# Titan_v1p0.net
KiCad netlist of a schematic drawn in EAGLE
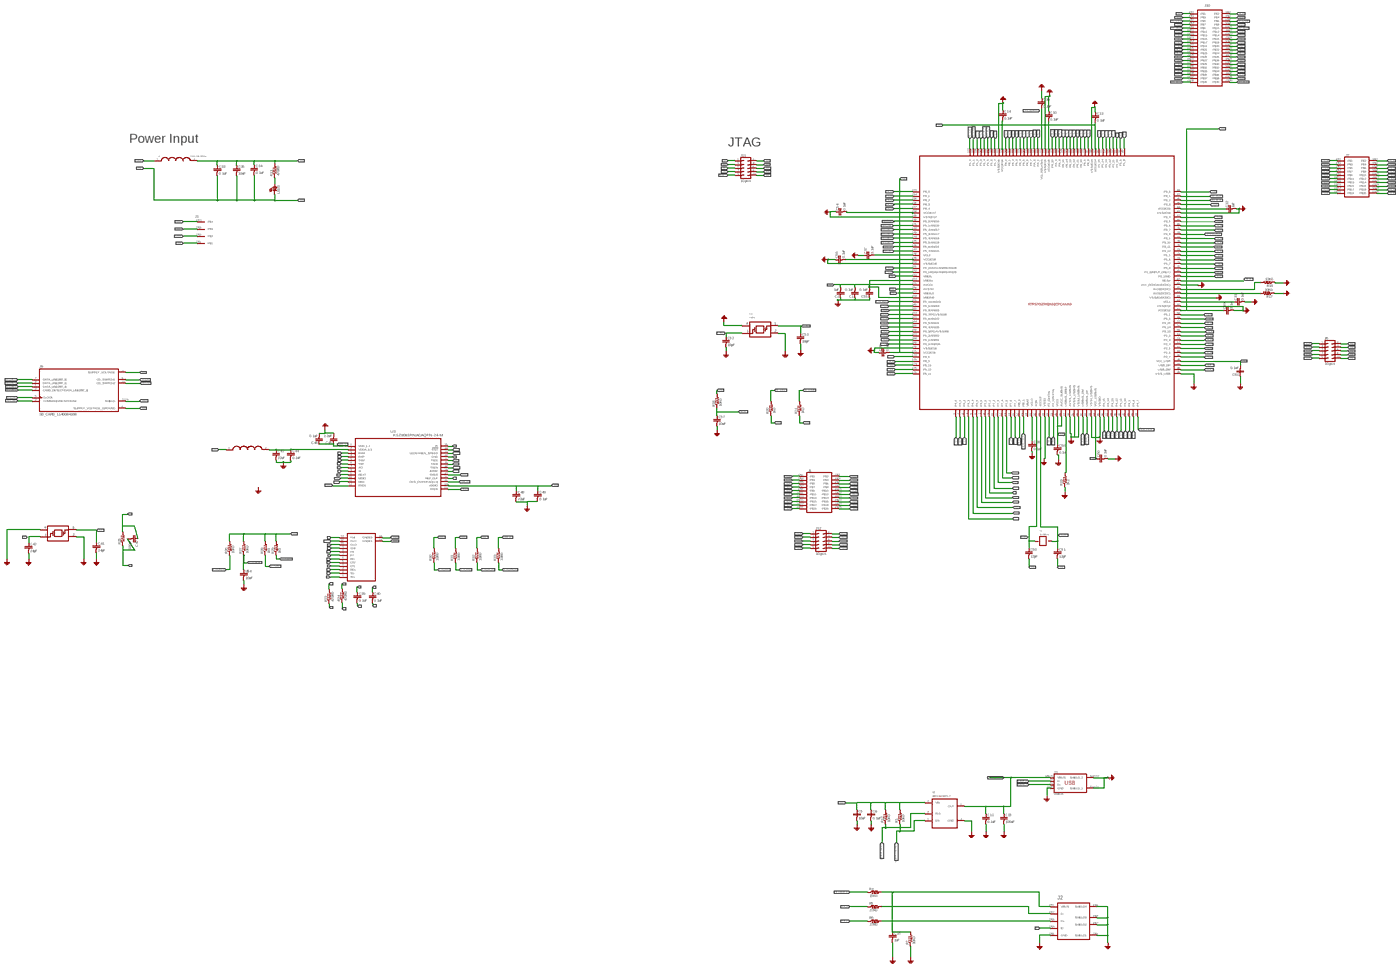
[diagram p0: schematic, sheet 1, overview]
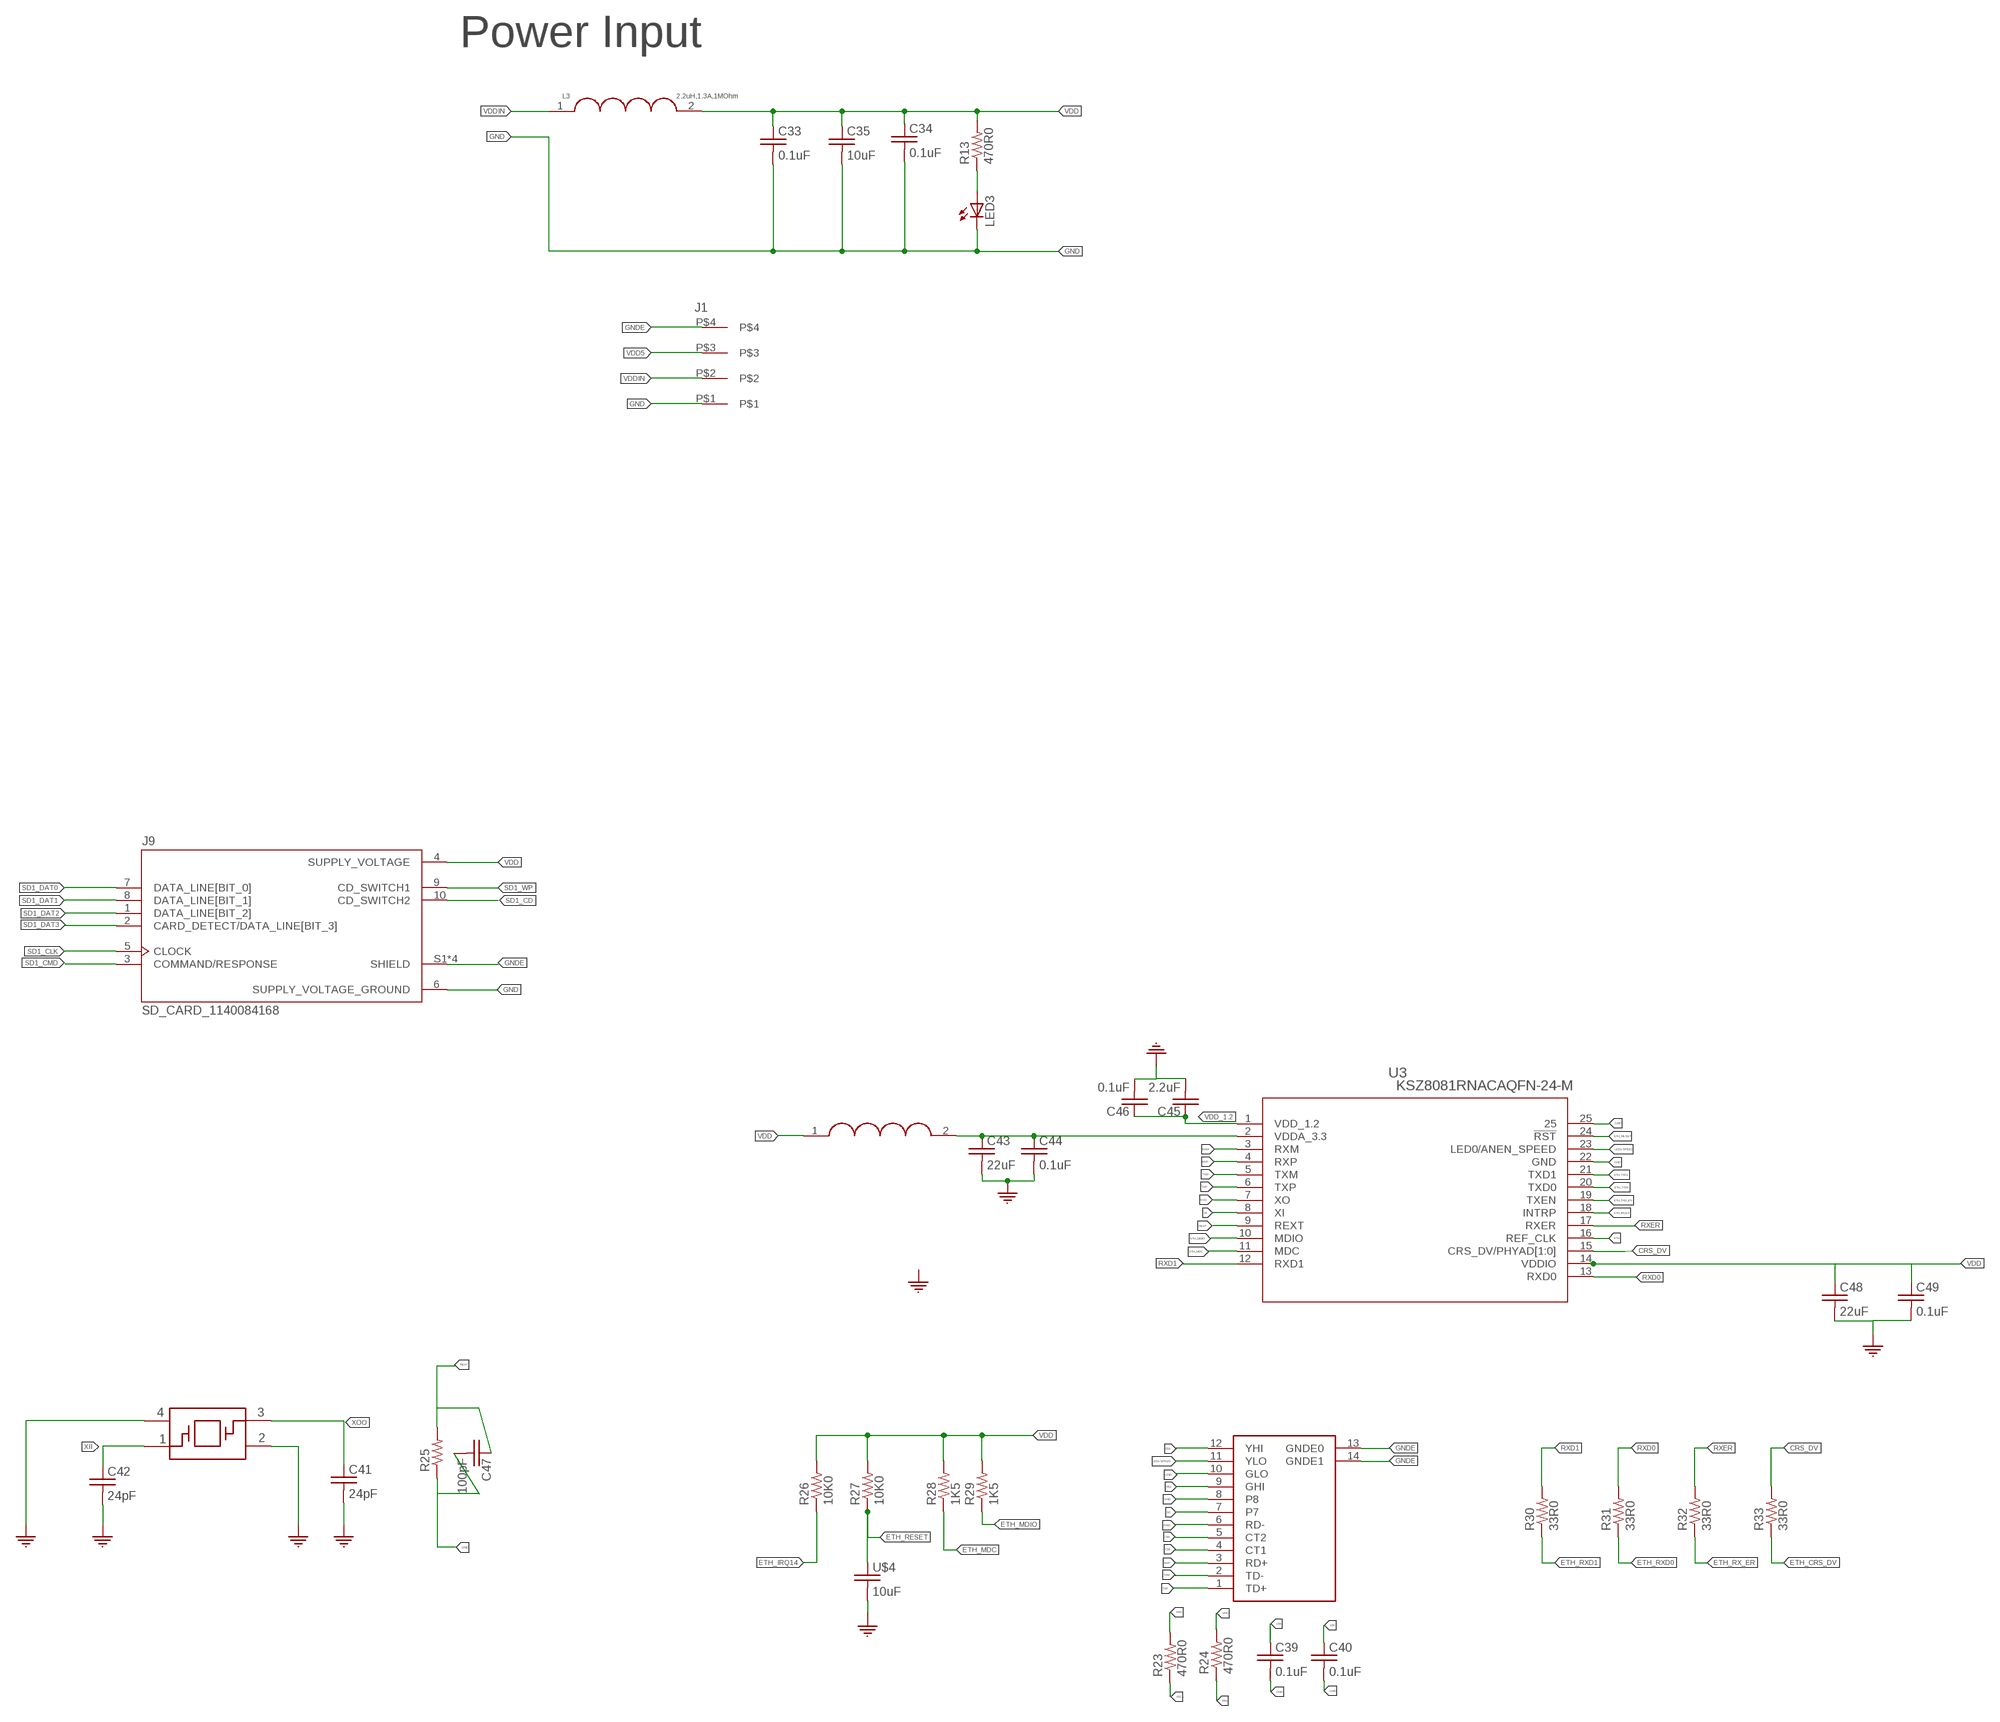
[diagram p1: schematic, sheet 1, part 1 of 4]
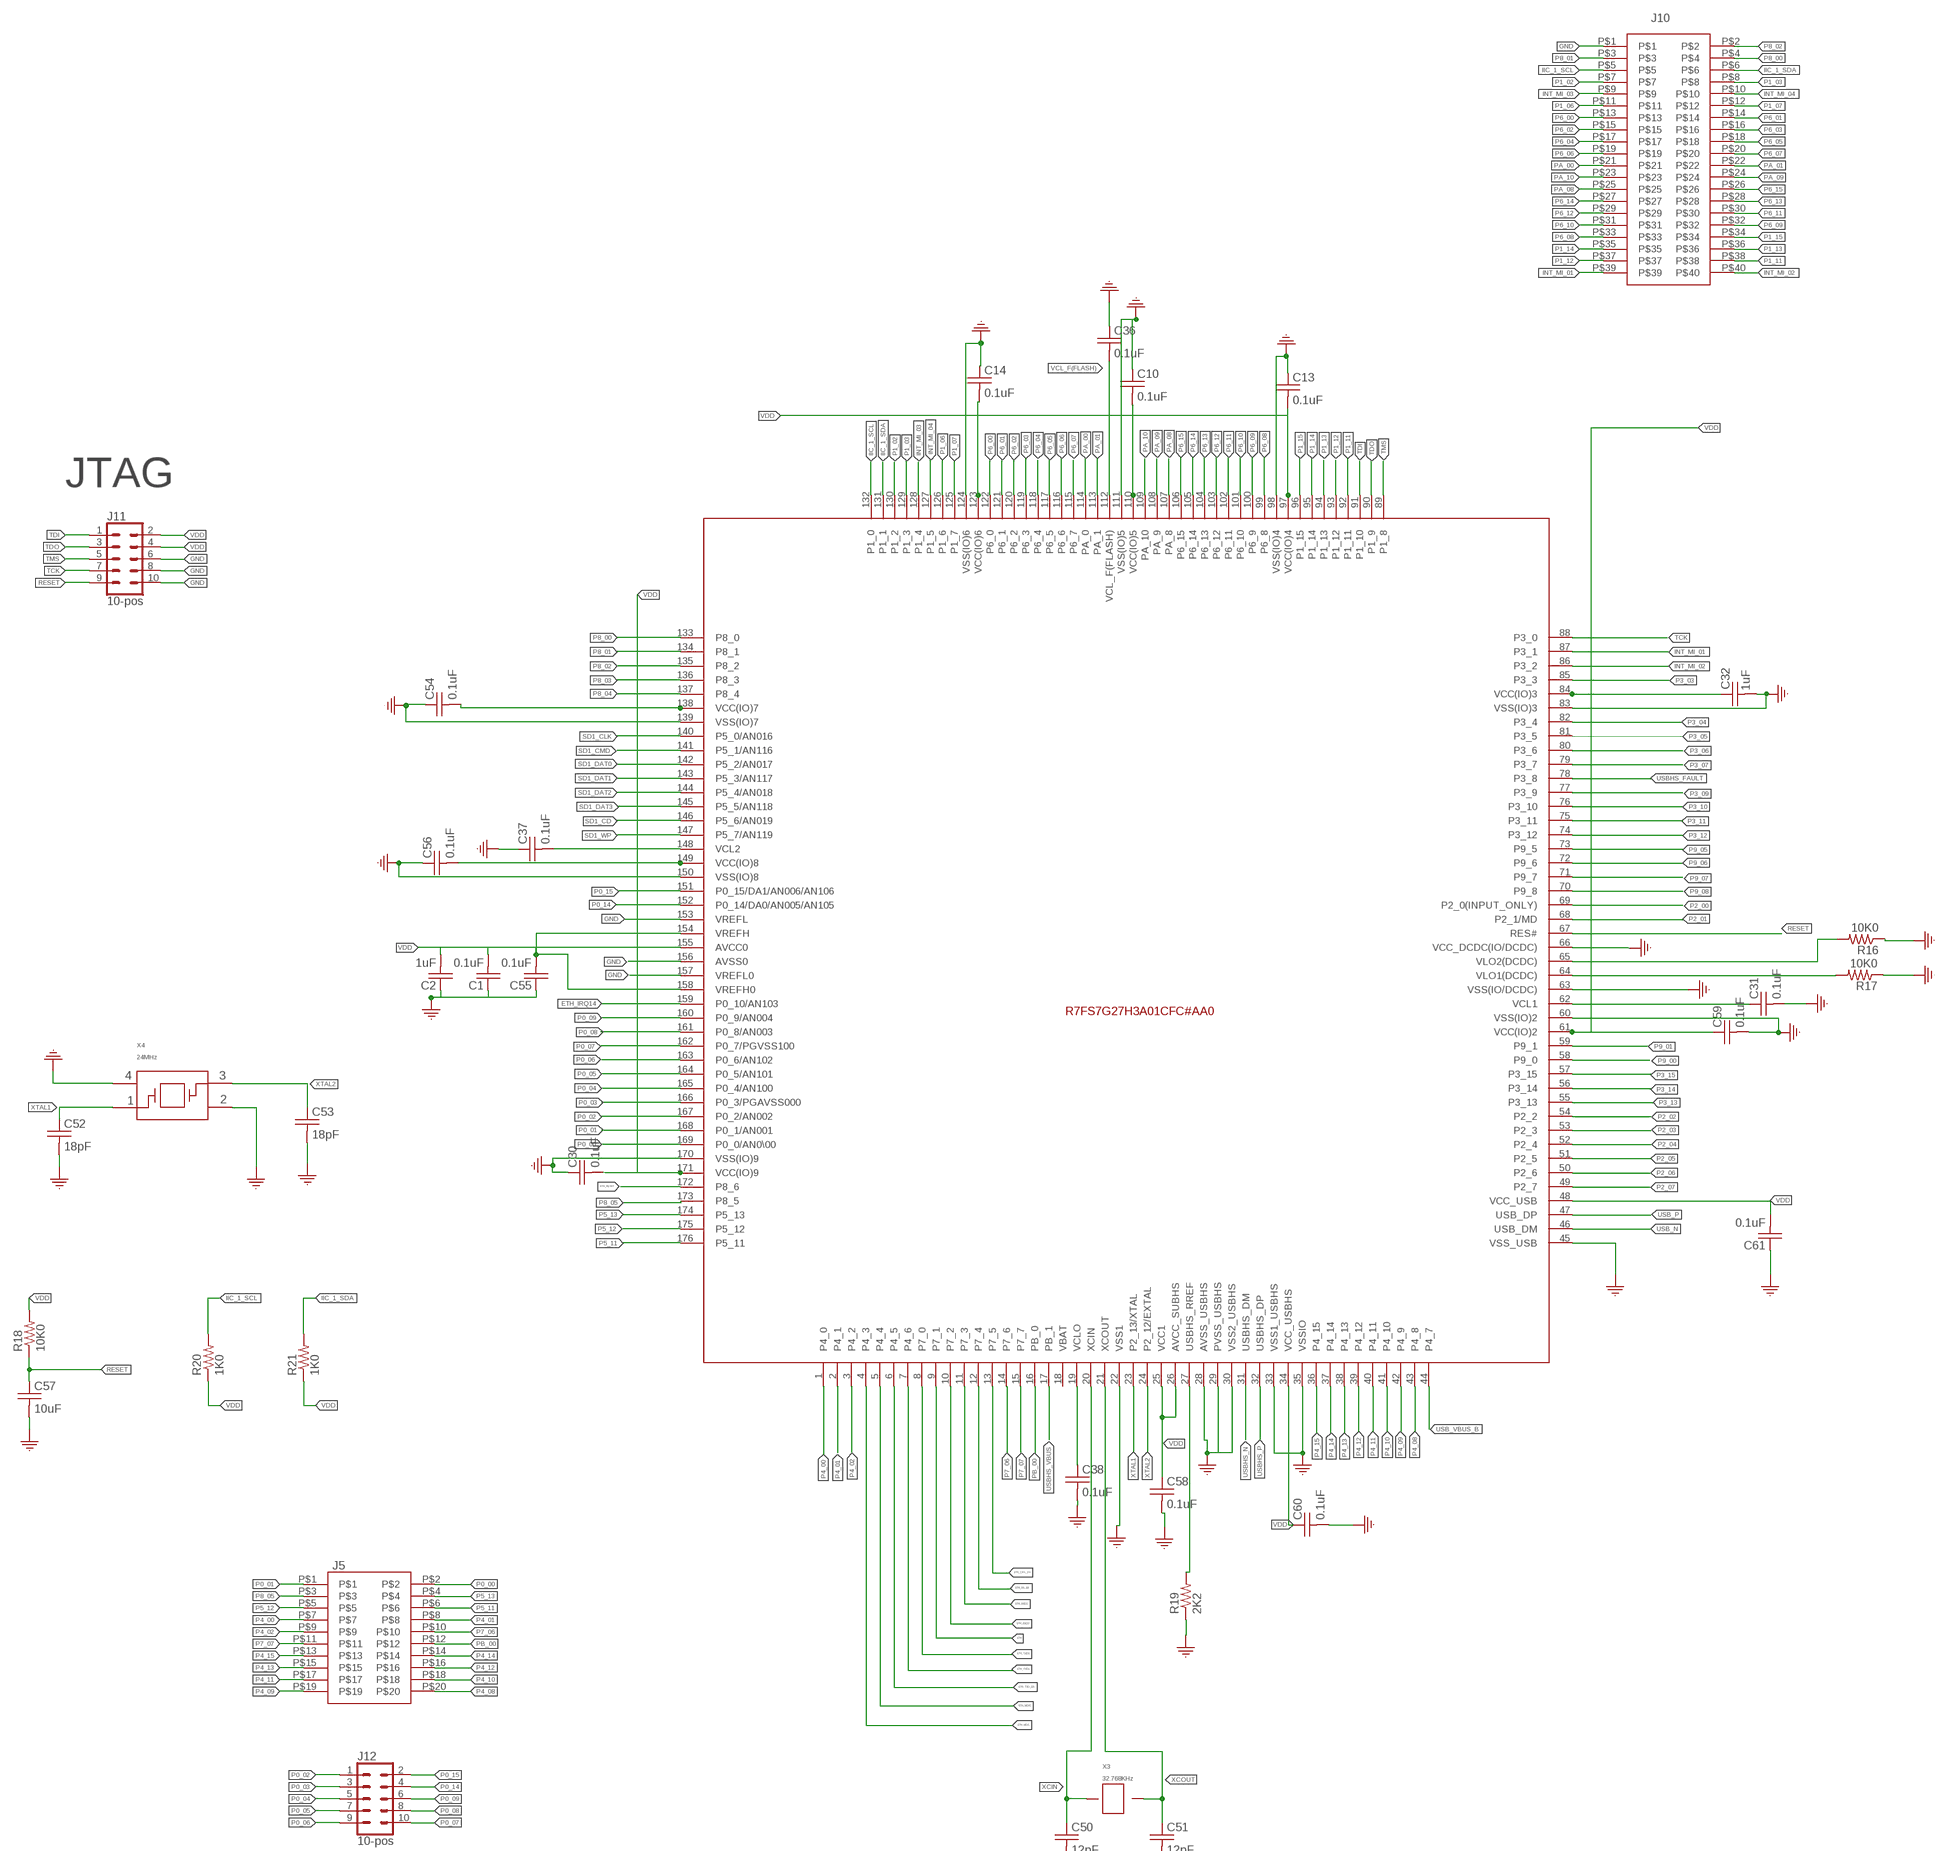
[diagram p2: schematic, sheet 1, part 2 of 4]
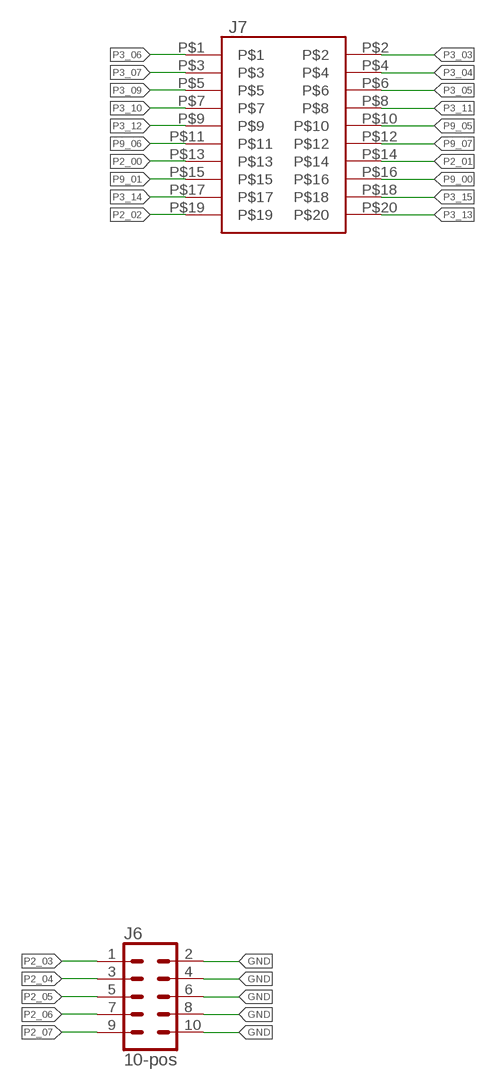
[diagram p3: schematic, sheet 1, part 3 of 4]
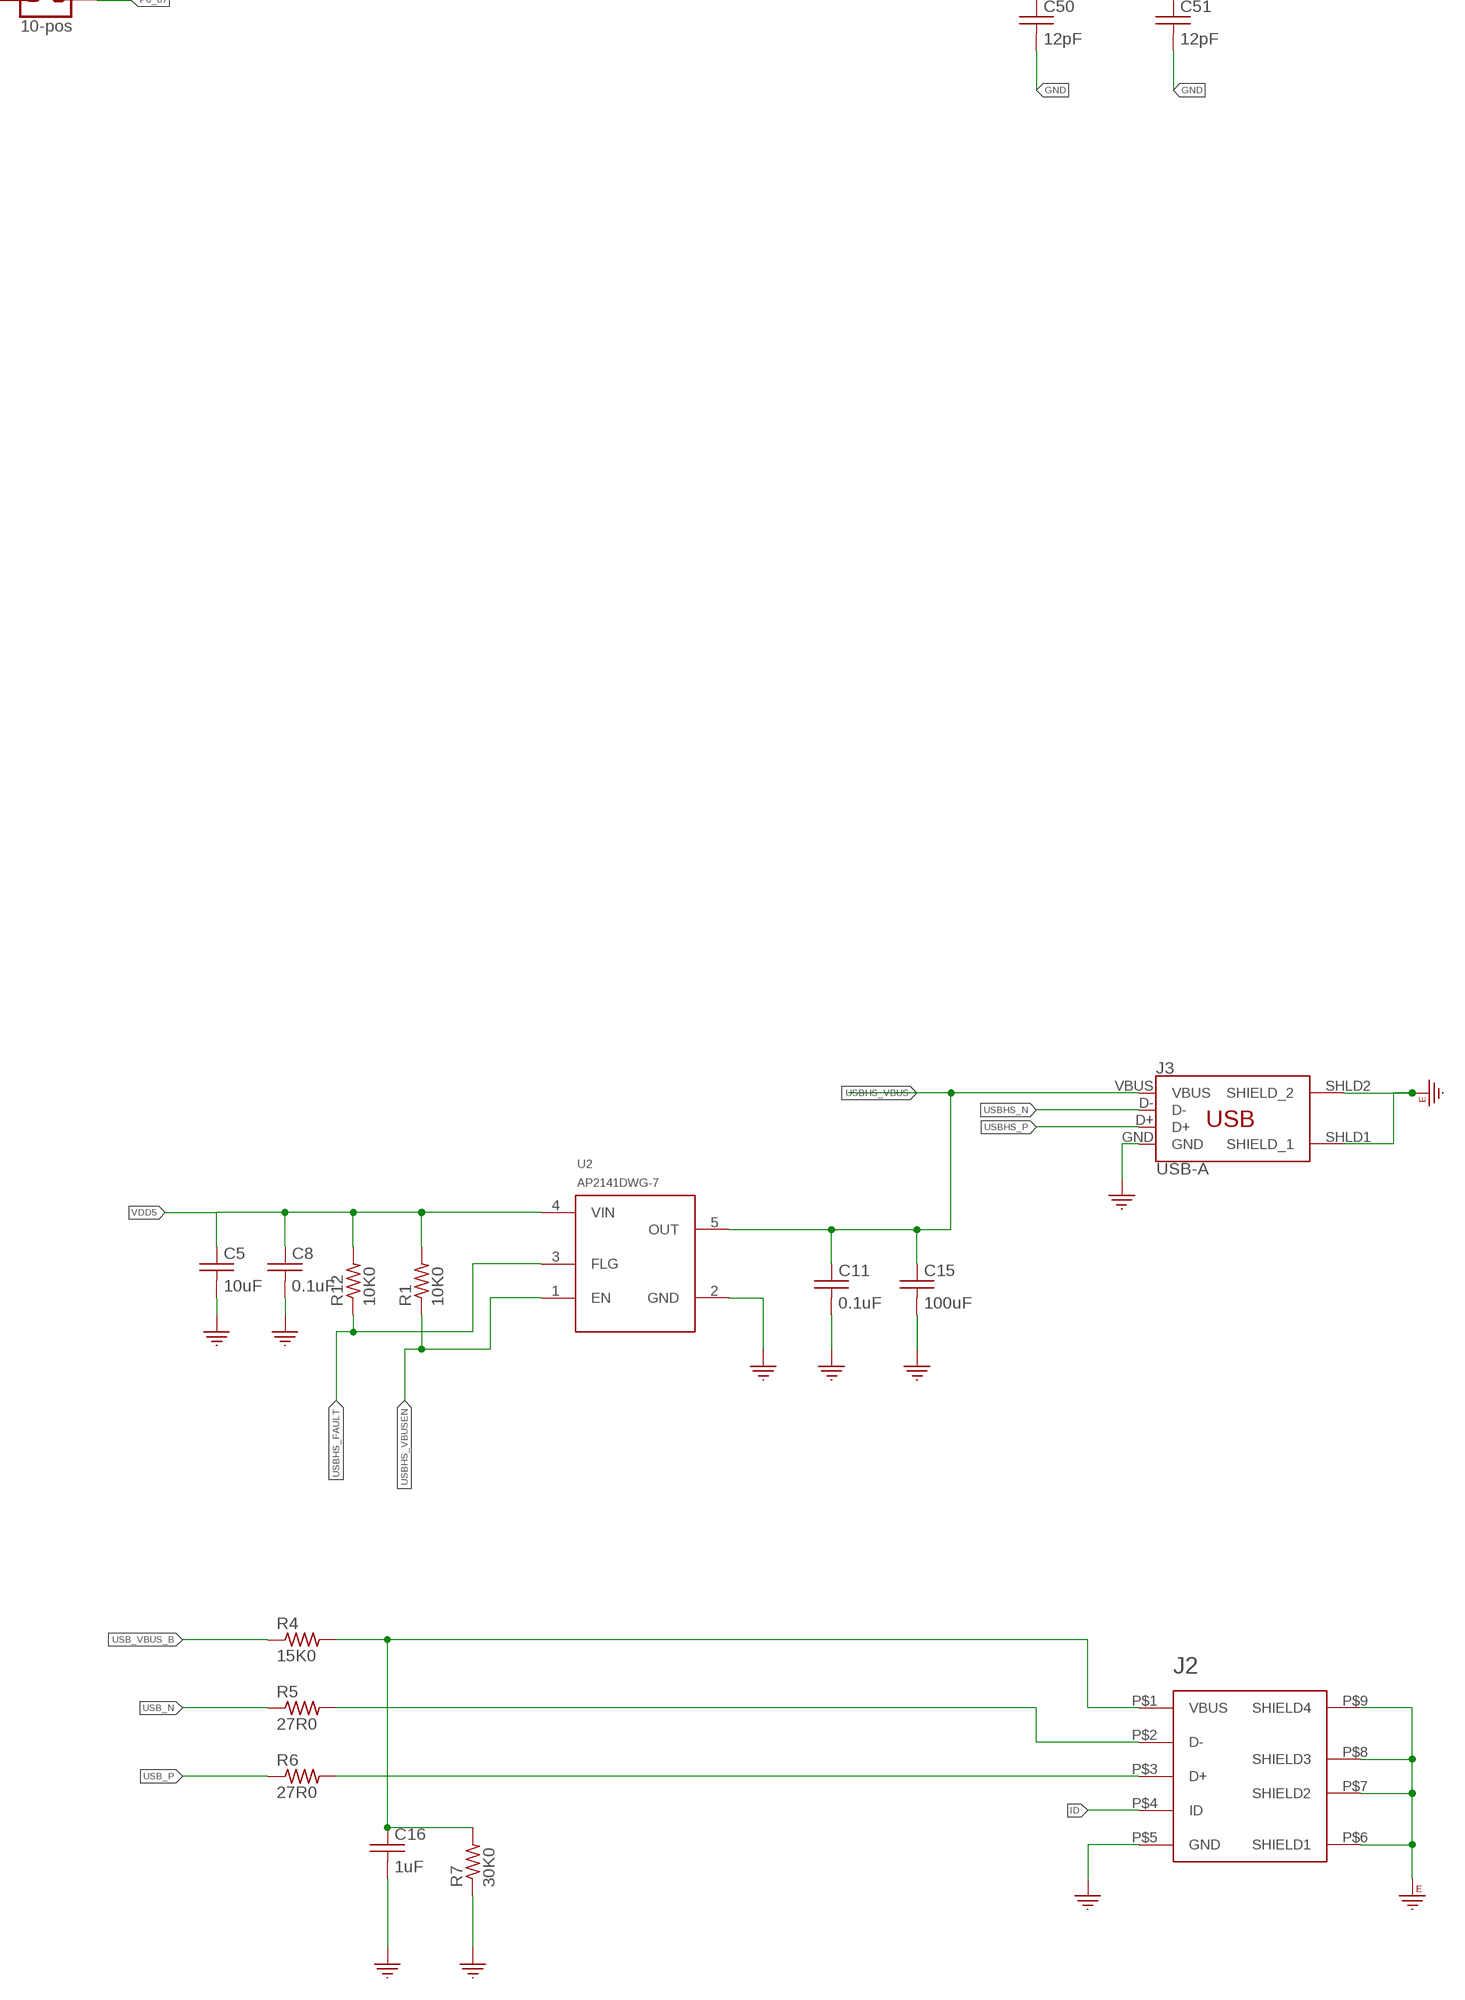
[diagram p4: schematic, sheet 1, part 4 of 4]

(export (version "E")
  (design (tool "Eeschema 10.0.6"))
  (components
    (comp (ref "C1")
      (value "0.1uF")
      (footprint "eagle-import:0402")
      (fields (field (name "PARTNO") "CL05F104ZO5NNNC"))
      (libsource (lib "eagle-import") (part "C_0402_0.1UF"))
    )
    (comp (ref "C2")
      (value "1uF")
      (footprint "eagle-import:0402")
      (fields (field (name "PARTNO") "CL05A105KO5NNNC"))
      (libsource (lib "eagle-import") (part "C_0402_1UF"))
    )
    (comp (ref "C5")
      (value "10uF")
      (footprint "eagle-import:0402")
      (fields (field (name "PARTNO") "CL05A106MP8NUB8"))
      (libsource (lib "eagle-import") (part "C_0402_10UF"))
    )
    (comp (ref "C8")
      (value "0.1uF")
      (footprint "eagle-import:0402")
      (fields (field (name "PARTNO") "CL05F104ZO5NNNC"))
      (libsource (lib "eagle-import") (part "C_0402_0.1UF"))
    )
    (comp (ref "C10")
      (value "0.1uF")
      (footprint "eagle-import:0402")
      (fields (field (name "PARTNO") "CL05F104ZO5NNNC"))
      (libsource (lib "eagle-import") (part "C_0402_0.1UF"))
    )
    (comp (ref "C11")
      (value "0.1uF")
      (footprint "eagle-import:0402")
      (fields (field (name "PARTNO") "CL05F104ZO5NNNC"))
      (libsource (lib "eagle-import") (part "C_0402_0.1UF"))
    )
    (comp (ref "C13")
      (value "0.1uF")
      (footprint "eagle-import:0402")
      (fields (field (name "PARTNO") "CL05F104ZO5NNNC"))
      (libsource (lib "eagle-import") (part "C_0402_0.1UF"))
    )
    (comp (ref "C14")
      (value "0.1uF")
      (footprint "eagle-import:0402")
      (fields (field (name "PARTNO") "CL05F104ZO5NNNC"))
      (libsource (lib "eagle-import") (part "C_0402_0.1UF"))
    )
    (comp (ref "C15")
      (value "100uF")
      (footprint "eagle-import:C1210")
      (fields (field (name "PARTNO") "TL8A0107M010D"))
      (libsource (lib "eagle-import") (part "C_1210"))
    )
    (comp (ref "C16")
      (value "1uF")
      (footprint "eagle-import:0402")
      (fields (field (name "PARTNO") "CL05A105KO5NNNC"))
      (libsource (lib "eagle-import") (part "C_0402_1UF"))
    )
    (comp (ref "C30")
      (value "0.1uF")
      (footprint "eagle-import:0402")
      (fields (field (name "PARTNO") "CL05F104ZO5NNNC"))
      (libsource (lib "eagle-import") (part "C_0402_0.1UF"))
    )
    (comp (ref "C31")
      (value "0.1uF")
      (footprint "eagle-import:0402")
      (fields (field (name "PARTNO") "CL05F104ZO5NNNC"))
      (libsource (lib "eagle-import") (part "C_0402_0.1UF"))
    )
    (comp (ref "C32")
      (value "1uF")
      (footprint "eagle-import:0402")
      (fields (field (name "PARTNO") "CL05A105KO5NNNC"))
      (libsource (lib "eagle-import") (part "C_0402_1UF"))
    )
    (comp (ref "C33")
      (value "0.1uF")
      (footprint "eagle-import:0402")
      (fields (field (name "PARTNO") "CL05F104ZO5NNNC"))
      (libsource (lib "eagle-import") (part "C_0402_0.1UF"))
    )
    (comp (ref "C34")
      (value "0.1uF")
      (footprint "eagle-import:0402")
      (fields (field (name "PARTNO") "CL05F104ZO5NNNC"))
      (libsource (lib "eagle-import") (part "C_0402_0.1UF"))
    )
    (comp (ref "C35")
      (value "10uF")
      (footprint "eagle-import:0402")
      (fields (field (name "PARTNO") "CL05A106MP8NUB8"))
      (libsource (lib "eagle-import") (part "C_0402_10UF"))
    )
    (comp (ref "C36")
      (value "0.1uF")
      (footprint "eagle-import:0402")
      (fields (field (name "PARTNO") "CL05F104ZO5NNNC"))
      (libsource (lib "eagle-import") (part "C_0402_0.1UF"))
    )
    (comp (ref "C37")
      (value "0.1uF")
      (footprint "eagle-import:0402")
      (fields (field (name "PARTNO") "CL05F104ZO5NNNC"))
      (libsource (lib "eagle-import") (part "C_0402_0.1UF"))
    )
    (comp (ref "C38")
      (value "0.1uF")
      (footprint "eagle-import:0402")
      (fields (field (name "PARTNO") "CL05F104ZO5NNNC"))
      (libsource (lib "eagle-import") (part "C_0402_0.1UF"))
    )
    (comp (ref "C39")
      (value "0.1uF")
      (footprint "eagle-import:0402")
      (fields (field (name "PARTNO") "CL05F104ZO5NNNC"))
      (libsource (lib "eagle-import") (part "C_0402_0.1UF"))
    )
    (comp (ref "C40")
      (value "0.1uF")
      (footprint "eagle-import:0402")
      (fields (field (name "PARTNO") "CL05F104ZO5NNNC"))
      (libsource (lib "eagle-import") (part "C_0402_0.1UF"))
    )
    (comp (ref "C41")
      (value "24pF")
      (footprint "eagle-import:0402")
      (fields (field (name "PARTNO") "CC0402GRNPO9BN240"))
      (libsource (lib "eagle-import") (part "C_0402_24PF"))
    )
    (comp (ref "C42")
      (value "24pF")
      (footprint "eagle-import:0402")
      (fields (field (name "PARTNO") "CC0402GRNPO9BN240"))
      (libsource (lib "eagle-import") (part "C_0402_24PF"))
    )
    (comp (ref "C43")
      (value "22uF")
      (footprint "eagle-import:0402")
      (fields (field (name "PARTNO") "CL05A226MQ5N6J8"))
      (libsource (lib "eagle-import") (part "C_0402_22UF"))
    )
    (comp (ref "C44")
      (value "0.1uF")
      (footprint "eagle-import:0402")
      (fields (field (name "PARTNO") "CL05F104ZO5NNNC"))
      (libsource (lib "eagle-import") (part "C_0402_0.1UF"))
    )
    (comp (ref "C45")
      (value "2.2uF")
      (footprint "eagle-import:0402")
      (fields (field (name "PARTNO") "GRM155C81C225ME15D"))
      (libsource (lib "eagle-import") (part "C_0402_2.2UF"))
    )
    (comp (ref "C46")
      (value "0.1uF")
      (footprint "eagle-import:0402")
      (fields (field (name "PARTNO") "CL05F104ZO5NNNC"))
      (libsource (lib "eagle-import") (part "C_0402_0.1UF"))
    )
    (comp (ref "C47")
      (value "100pF")
      (footprint "eagle-import:0402")
      (fields (field (name "PARTNO") "CL05C101JB5NNNC"))
      (libsource (lib "eagle-import") (part "C_0402_100PF"))
    )
    (comp (ref "C48")
      (value "22uF")
      (footprint "eagle-import:0402")
      (fields (field (name "PARTNO") "CL05A226MQ5N6J8"))
      (libsource (lib "eagle-import") (part "C_0402_22UF"))
    )
    (comp (ref "C49")
      (value "0.1uF")
      (footprint "eagle-import:0402")
      (fields (field (name "PARTNO") "CL05F104ZO5NNNC"))
      (libsource (lib "eagle-import") (part "C_0402_0.1UF"))
    )
    (comp (ref "C50")
      (value "12pF")
      (footprint "eagle-import:0402")
      (fields (field (name "PARTNO") "CL05C120JB5NNNC"))
      (libsource (lib "eagle-import") (part "C_0402_12PF"))
    )
    (comp (ref "C51")
      (value "12pF")
      (footprint "eagle-import:0402")
      (fields (field (name "PARTNO") "CL05C120JB5NNNC"))
      (libsource (lib "eagle-import") (part "C_0402_12PF"))
    )
    (comp (ref "C52")
      (value "18pF")
      (footprint "eagle-import:0402")
      (fields (field (name "PARTNO") "UMK105CG180JV-F"))
      (libsource (lib "eagle-import") (part "C_0402_18PF"))
    )
    (comp (ref "C53")
      (value "18pF")
      (footprint "eagle-import:0402")
      (fields (field (name "PARTNO") "UMK105CG180JV-F"))
      (libsource (lib "eagle-import") (part "C_0402_18PF"))
    )
    (comp (ref "C54")
      (value "0.1uF")
      (footprint "eagle-import:0402")
      (fields (field (name "PARTNO") "CL05F104ZO5NNNC"))
      (libsource (lib "eagle-import") (part "C_0402_0.1UF"))
    )
    (comp (ref "C55")
      (value "0.1uF")
      (footprint "eagle-import:0402")
      (fields (field (name "PARTNO") "CL05F104ZO5NNNC"))
      (libsource (lib "eagle-import") (part "C_0402_0.1UF"))
    )
    (comp (ref "C56")
      (value "0.1uF")
      (footprint "eagle-import:0402")
      (fields (field (name "PARTNO") "CL05F104ZO5NNNC"))
      (libsource (lib "eagle-import") (part "C_0402_0.1UF"))
    )
    (comp (ref "C57")
      (value "10uF")
      (footprint "eagle-import:0402")
      (fields (field (name "PARTNO") "CL05A106MP8NUB8"))
      (libsource (lib "eagle-import") (part "C_0402_10UF"))
    )
    (comp (ref "C58")
      (value "0.1uF")
      (footprint "eagle-import:0402")
      (fields (field (name "PARTNO") "CL05F104ZO5NNNC"))
      (libsource (lib "eagle-import") (part "C_0402_0.1UF"))
    )
    (comp (ref "C59")
      (value "0.1uF")
      (footprint "eagle-import:0402")
      (fields (field (name "PARTNO") "CL05F104ZO5NNNC"))
      (libsource (lib "eagle-import") (part "C_0402_0.1UF"))
    )
    (comp (ref "C60")
      (value "0.1uF")
      (footprint "eagle-import:0402")
      (fields (field (name "PARTNO") "CL05F104ZO5NNNC"))
      (libsource (lib "eagle-import") (part "C_0402_0.1UF"))
    )
    (comp (ref "C61")
      (value "0.1uF")
      (footprint "eagle-import:0402")
      (fields (field (name "PARTNO") "CL05F104ZO5NNNC"))
      (libsource (lib "eagle-import") (part "C_0402_0.1UF"))
    )
    (comp (ref "FB2/2")
      (value "120Ohm")
      (footprint "eagle-import:0603")
      (fields (field (name "PARTNO") "BLM18PG121SN1D"))
      (libsource (lib "eagle-import") (part "FB_0603_120_OHM0603"))
    )
    (comp (ref "J1")
      (value "4-pos")
      (footprint "eagle-import:1X4_3.81MM_PITCH")
      (fields (field (name "PARTNO") "691322310004"))
      (libsource (lib "eagle-import") (part "3.81MM_1_X_4_RT_ANGLE_PLUG_HEADER"))
    )
    (comp (ref "J2")
      (value "USB-B-Micro")
      (footprint "eagle-import:USB_MICRO-B")
      (fields (field (name "PARTNO") "10118192-0002LF"))
      (libsource (lib "eagle-import") (part "USB_MICRO-B"))
    )
    (comp (ref "J3")
      (value "USB-A")
      (footprint "eagle-import:USB_A_SMT")
      (fields (field (name "PARTNO") "87583-3010RPALF"))
      (libsource (lib "eagle-import") (part "USB_A"))
    )
    (comp (ref "J4")
      (value "RJ45")
      (footprint "eagle-import:RJ45_TH_ELEC")
      (fields (field (name "PARTNO") "13F-64GYD2PL2NL"))
      (libsource (lib "eagle-import") (part "RJ45_WITH_ELEC"))
    )
    (comp (ref "J5")
      (value "20-pos")
      (footprint "eagle-import:2_X_10_.1_INCH")
      (fields (field (name "PARTNO") "67996-420HLF"))
      (libsource (lib "eagle-import") (part "2_X_10_HEADER_GENERIC"))
    )
    (comp (ref "J6")
      (value "10-pos")
      (footprint "eagle-import:2X5")
      (fields (field (name "PARTNO") "PH2RA-10-UA"))
      (libsource (lib "eagle-import") (part "CONN_05X2_RAPTH"))
    )
    (comp (ref "J7")
      (value "20-pos")
      (footprint "eagle-import:2_X_10_.1_INCH")
      (fields (field (name "PARTNO") "67996-420HLF"))
      (libsource (lib "eagle-import") (part "2_X_10_HEADER_GENERIC"))
    )
    (comp (ref "J9")
      (value "SD_CARD_1140084168")
      (footprint "eagle-import:AMPHENOL_1140084168")
      (fields (field (name "MF") "Amphenol ICC") (field (name "PARTNO") "114-00841-68"))
      (libsource (lib "eagle-import") (part "SD_CARD_1140084168"))
    )
    (comp (ref "J10")
      (value "40-pos")
      (footprint "eagle-import:HEADER_2_X_20_.1_INCH")
      (fields (field (name "PARTNO") "61304021021"))
      (libsource (lib "eagle-import") (part "HEADER_2_X_20_GENERIC"))
    )
    (comp (ref "J11")
      (value "10-pos")
      (footprint "eagle-import:2X5")
      (fields (field (name "PARTNO") "PH2RA-10-UA"))
      (libsource (lib "eagle-import") (part "CONN_05X2_RAPTH"))
    )
    (comp (ref "J12")
      (value "10-pos")
      (footprint "eagle-import:2X5")
      (fields (field (name "PARTNO") "PH2RA-10-UA"))
      (libsource (lib "eagle-import") (part "CONN_05X2_RAPTH"))
    )
    (comp (ref "L3")
      (value "2.2uH,1.3A,1MOhm")
      (footprint "eagle-import:1008")
      (fields (field (name "PARTNO") "LQM2HPN2R2MG0L"))
      (libsource (lib "eagle-import") (part "INDUCTOR_1008_2.2_MH_1.3A"))
    )
    (comp (ref "LED3")
      (value "Green")
      (footprint "eagle-import:0805")
      (fields (field (name "PARTNO") "LG R971-KN-1"))
      (libsource (lib "eagle-import") (part "LED_0805_GREEN"))
    )
    (comp (ref "R1")
      (value "10K0")
      (footprint "eagle-import:0402")
      (fields (field (name "PARTNO") "RMCF0402JT10K0"))
      (libsource (lib "eagle-import") (part "R_0402_10K0"))
    )
    (comp (ref "R4")
      (value "15K0")
      (footprint "eagle-import:0402")
      (fields (field (name "PARTNO") "RMCF0402JT15K0"))
      (libsource (lib "eagle-import") (part "R_0402_15K0"))
    )
    (comp (ref "R5")
      (value "27R0")
      (footprint "eagle-import:0402")
      (fields (field (name "PARTNO") "RMCF0402JT27R0"))
      (libsource (lib "eagle-import") (part "R_0402_27R0"))
    )
    (comp (ref "R6")
      (value "27R0")
      (footprint "eagle-import:0402")
      (fields (field (name "PARTNO") "RMCF0402JT27R0"))
      (libsource (lib "eagle-import") (part "R_0402_27R0"))
    )
    (comp (ref "R7")
      (value "30K0")
      (footprint "eagle-import:0402")
      (fields (field (name "PARTNO") "RC0402JR-0730KL"))
      (libsource (lib "eagle-import") (part "R_0402_30K0"))
    )
    (comp (ref "R12")
      (value "10K0")
      (footprint "eagle-import:0402")
      (fields (field (name "PARTNO") "RMCF0402JT10K0"))
      (libsource (lib "eagle-import") (part "R_0402_10K0"))
    )
    (comp (ref "R13")
      (value "470R0")
      (footprint "eagle-import:0402")
      (fields (field (name "PARTNO") "RMCF0402JT470R"))
      (libsource (lib "eagle-import") (part "R_0402_470R0"))
    )
    (comp (ref "R16")
      (value "10K0")
      (footprint "eagle-import:0402")
      (fields (field (name "PARTNO") "RMCF0402JT10K0"))
      (libsource (lib "eagle-import") (part "R_0402_10K0"))
    )
    (comp (ref "R17")
      (value "10K0")
      (footprint "eagle-import:0402")
      (fields (field (name "PARTNO") "RMCF0402JT10K0"))
      (libsource (lib "eagle-import") (part "R_0402_10K0"))
    )
    (comp (ref "R18")
      (value "10K0")
      (footprint "eagle-import:0402")
      (fields (field (name "PARTNO") "RMCF0402JT10K0"))
      (libsource (lib "eagle-import") (part "R_0402_10K0"))
    )
    (comp (ref "R19")
      (value "2K2")
      (footprint "eagle-import:0402")
      (fields (field (name "PARTNO") "RMCF0402JT2K20"))
      (libsource (lib "eagle-import") (part "R_0402_2K2"))
    )
    (comp (ref "R20")
      (value "1K0")
      (footprint "eagle-import:0402")
      (fields (field (name "PARTNO") "CRG0402J1K0"))
      (libsource (lib "eagle-import") (part "R_0402_1K0"))
    )
    (comp (ref "R21")
      (value "1K0")
      (footprint "eagle-import:0402")
      (fields (field (name "PARTNO") "CRG0402J1K0"))
      (libsource (lib "eagle-import") (part "R_0402_1K0"))
    )
    (comp (ref "R23")
      (value "470R0")
      (footprint "eagle-import:0402")
      (fields (field (name "PARTNO") "RMCF0402JT470R"))
      (libsource (lib "eagle-import") (part "R_0402_470R0"))
    )
    (comp (ref "R24")
      (value "470R0")
      (footprint "eagle-import:0402")
      (fields (field (name "PARTNO") "RMCF0402JT470R"))
      (libsource (lib "eagle-import") (part "R_0402_470R0"))
    )
    (comp (ref "R25")
      (value "6K49")
      (footprint "eagle-import:0402")
      (fields (field (name "PARTNO") "RMCF0402FT6K49"))
      (libsource (lib "eagle-import") (part "R_0402_6K49"))
    )
    (comp (ref "R26")
      (value "10K0")
      (footprint "eagle-import:0402")
      (fields (field (name "PARTNO") "RMCF0402JT10K0"))
      (libsource (lib "eagle-import") (part "R_0402_10K0"))
    )
    (comp (ref "R27")
      (value "10K0")
      (footprint "eagle-import:0402")
      (fields (field (name "PARTNO") "RMCF0402JT10K0"))
      (libsource (lib "eagle-import") (part "R_0402_10K0"))
    )
    (comp (ref "R28")
      (value "1K5")
      (footprint "eagle-import:0402")
      (fields (field (name "PARTNO") "RMCF0402JT1K50"))
      (libsource (lib "eagle-import") (part "R_0402_1K5"))
    )
    (comp (ref "R29")
      (value "1K5")
      (footprint "eagle-import:0402")
      (fields (field (name "PARTNO") "RMCF0402JT1K50"))
      (libsource (lib "eagle-import") (part "R_0402_1K5"))
    )
    (comp (ref "R30")
      (value "33R0")
      (footprint "eagle-import:0402")
      (fields (field (name "PARTNO") "RMCF0402JT33R0"))
      (libsource (lib "eagle-import") (part "R_0402_33R0"))
    )
    (comp (ref "R31")
      (value "33R0")
      (footprint "eagle-import:0402")
      (fields (field (name "PARTNO") "RMCF0402JT33R0"))
      (libsource (lib "eagle-import") (part "R_0402_33R0"))
    )
    (comp (ref "R32")
      (value "33R0")
      (footprint "eagle-import:0402")
      (fields (field (name "PARTNO") "RMCF0402JT33R0"))
      (libsource (lib "eagle-import") (part "R_0402_33R0"))
    )
    (comp (ref "R33")
      (value "33R0")
      (footprint "eagle-import:0402")
      (fields (field (name "PARTNO") "RMCF0402JT33R0"))
      (libsource (lib "eagle-import") (part "R_0402_33R0"))
    )
    (comp (ref "U$4")
      (value "10uF")
      (footprint "eagle-import:0402")
      (fields (field (name "PARTNO") "CL05A106MP8NUB8"))
      (libsource (lib "eagle-import") (part "C_0402_10UF"))
    )
    (comp (ref "U2")
      (value "AP2151DWG-7")
      (footprint "eagle-import:SOT-23-5")
      (fields (field (name "PARTNO") "AP2151WG-7"))
      (libsource (lib "eagle-import") (part "AP2151DWG-7"))
    )
    (comp (ref "U3")
      (value "KSZ8081RNACAQFN-24-M")
      (footprint "eagle-import:QFN-24-M")
      (fields (field (name "PARTNO") "KSZ8081RNACA"))
      (libsource (lib "eagle-import") (part "KSZ8081RNACAQFN-24-M"))
    )
    (comp (ref "U4")
      (value "S7G2LQFP176")
      (footprint "eagle-import:LQFP176_24X24")
      (fields (field (name "PARTNO") "R7FS7G27H3A01CFC#AA0"))
      (libsource (lib "eagle-import") (part "S7G2_X_176"))
    )
    (comp (ref "U5")
      (value "25MHz")
      (footprint "eagle-import:SMD_3225")
      (fields (field (name "PARTNO") "FA-238 25.0000MB-B3"))
      (libsource (lib "eagle-import") (part "XTAL_25_MHZ"))
    )
    (comp (ref "X3")
      (value "32.768KHz")
      (footprint "eagle-import:SMD_X_2_PADS")
      (fields (field (name "PARTNO") "ABS07-32.768KHZ-T"))
      (libsource (lib "eagle-import") (part "XTAL_32.768KHZ"))
    )
    (comp (ref "X4")
      (value "24MHz")
      (footprint "eagle-import:SMD_3225")
      (fields (field (name "PARTNO") "FA-238 24.0000MB-C3 "))
      (libsource (lib "eagle-import") (part "XTAL_24_MHZ"))
    )
  )
  (nets
    (net (code "1") (name "C58") (class "Default")
      (node (ref "C39") (pin "P$1") (pinfunction "1_P$1") (pintype "passive"))
      (node (ref "J4") (pin "4") (pinfunction "CT1_4") (pintype "bidirectional"))
    )
    (net (code "2") (name "C60") (class "Default")
      (node (ref "C40") (pin "P$1") (pinfunction "1_P$1") (pintype "passive"))
      (node (ref "J4") (pin "5") (pinfunction "CT2_5") (pintype "bidirectional"))
    )
    (net (code "3") (name "CRS_DV") (class "Default")
      (node (ref "R33") (pin "P$2") (pinfunction "2_P$2") (pintype "passive"))
      (node (ref "U3") (pin "15") (pinfunction "CRS_DV/PHYAD[1:0]_15") (pintype "bidirectional"))
    )
    (net (code "4") (name "ETH") (class "Default")
      (node (ref "U3") (pin "16") (pinfunction "REF_CLK_16") (pintype "bidirectional"))
      (node (ref "U4") (pin "9") (pinfunction "P7_1_9") (pintype "bidirectional"))
    )
    (net (code "5") (name "ETH_CRS_DV") (class "Default")
      (node (ref "R33") (pin "P$1") (pinfunction "1_P$1") (pintype "passive"))
      (node (ref "U4") (pin "13") (pinfunction "P7_5_13") (pintype "bidirectional"))
    )
    (net (code "6") (name "ETH_IRQ14") (class "Default")
      (node (ref "R26") (pin "P$1") (pinfunction "1_P$1") (pintype "passive"))
      (node (ref "U3") (pin "18") (pinfunction "INTRP_18") (pintype "bidirectional"))
      (node (ref "U4") (pin "159") (pinfunction "P0_10/AN103_159") (pintype "bidirectional"))
    )
    (net (code "7") (name "ETH_MDC") (class "Default")
      (node (ref "R28") (pin "P$1") (pinfunction "1_P$1") (pintype "passive"))
      (node (ref "U3") (pin "11") (pinfunction "MDC_11") (pintype "input"))
      (node (ref "U4") (pin "4") (pinfunction "P4_3_4") (pintype "bidirectional"))
    )
    (net (code "8") (name "ETH_MDIO") (class "Default")
      (node (ref "R29") (pin "P$1") (pinfunction "1_P$1") (pintype "passive"))
      (node (ref "U3") (pin "10") (pinfunction "MDIO_10") (pintype "bidirectional"))
      (node (ref "U4") (pin "5") (pinfunction "P4_4_5") (pintype "bidirectional"))
    )
    (net (code "9") (name "ETH_RESET") (class "Default")
      (node (ref "R27") (pin "P$1") (pinfunction "1_P$1") (pintype "passive"))
      (node (ref "U$4") (pin "P$1") (pinfunction "1_P$1") (pintype "passive"))
      (node (ref "U3") (pin "24") (pinfunction "~{RST}_24") (pintype "input"))
      (node (ref "U4") (pin "172") (pinfunction "P8_6_172") (pintype "bidirectional"))
    )
    (net (code "10") (name "ETH_RXD0") (class "Default")
      (node (ref "R31") (pin "P$1") (pinfunction "1_P$1") (pintype "passive"))
      (node (ref "U4") (pin "10") (pinfunction "P7_2_10") (pintype "bidirectional"))
    )
    (net (code "11") (name "ETH_RXD1") (class "Default")
      (node (ref "R30") (pin "P$1") (pinfunction "1_P$1") (pintype "passive"))
      (node (ref "U4") (pin "11") (pinfunction "P7_3_11") (pintype "bidirectional"))
    )
    (net (code "12") (name "ETH_RX_ER") (class "Default")
      (node (ref "R32") (pin "P$1") (pinfunction "1_P$1") (pintype "passive"))
      (node (ref "U4") (pin "12") (pinfunction "P7_4_12") (pintype "bidirectional"))
    )
    (net (code "13") (name "ETH_TXD0") (class "Default")
      (node (ref "U3") (pin "20") (pinfunction "TXD0_20") (pintype "input"))
      (node (ref "U4") (pin "8") (pinfunction "P7_0_8") (pintype "bidirectional"))
    )
    (net (code "14") (name "ETH_TXD1") (class "Default")
      (node (ref "U3") (pin "21") (pinfunction "TXD1_21") (pintype "bidirectional"))
      (node (ref "U4") (pin "7") (pinfunction "P4_6_7") (pintype "bidirectional"))
    )
    (net (code "15") (name "ETH_TXD_EN") (class "Default")
      (node (ref "U3") (pin "19") (pinfunction "TXEN_19") (pintype "input"))
      (node (ref "U4") (pin "6") (pinfunction "P4_5_6") (pintype "bidirectional"))
    )
    (net (code "16") (name "GND") (class "Default")
      (node (ref "C1") (pin "P$1") (pinfunction "1_P$1") (pintype "passive"))
      (node (ref "C10") (pin "P$1") (pinfunction "1_P$1") (pintype "passive"))
      (node (ref "C11") (pin "P$2") (pinfunction "2_P$2") (pintype "passive"))
      (node (ref "C13") (pin "P$1") (pinfunction "1_P$1") (pintype "passive"))
      (node (ref "C14") (pin "P$1") (pinfunction "1_P$1") (pintype "passive"))
      (node (ref "C15") (pin "2") (pinfunction "2_2") (pintype "passive"))
      (node (ref "C16") (pin "P$2") (pinfunction "2_P$2") (pintype "passive"))
      (node (ref "C2") (pin "P$1") (pinfunction "1_P$1") (pintype "passive"))
      (node (ref "C30") (pin "P$1") (pinfunction "1_P$1") (pintype "passive"))
      (node (ref "C31") (pin "P$2") (pinfunction "2_P$2") (pintype "passive"))
      (node (ref "C32") (pin "P$2") (pinfunction "2_P$2") (pintype "passive"))
      (node (ref "C33") (pin "P$2") (pinfunction "2_P$2") (pintype "passive"))
      (node (ref "C34") (pin "P$2") (pinfunction "2_P$2") (pintype "passive"))
      (node (ref "C35") (pin "P$2") (pinfunction "2_P$2") (pintype "passive"))
      (node (ref "C36") (pin "P$1") (pinfunction "1_P$1") (pintype "passive"))
      (node (ref "C37") (pin "P$1") (pinfunction "1_P$1") (pintype "passive"))
      (node (ref "C38") (pin "P$2") (pinfunction "2_P$2") (pintype "passive"))
      (node (ref "C39") (pin "P$2") (pinfunction "2_P$2") (pintype "passive"))
      (node (ref "C40") (pin "P$2") (pinfunction "2_P$2") (pintype "passive"))
      (node (ref "C41") (pin "P$2") (pinfunction "2_P$2") (pintype "passive"))
      (node (ref "C42") (pin "P$2") (pinfunction "2_P$2") (pintype "passive"))
      (node (ref "C43") (pin "P$2") (pinfunction "2_P$2") (pintype "passive"))
      (node (ref "C44") (pin "P$2") (pinfunction "2_P$2") (pintype "passive"))
      (node (ref "C45") (pin "P$2") (pinfunction "2_P$2") (pintype "passive"))
      (node (ref "C46") (pin "P$2") (pinfunction "2_P$2") (pintype "passive"))
      (node (ref "C47") (pin "P$2") (pinfunction "2_P$2") (pintype "passive"))
      (node (ref "C48") (pin "P$2") (pinfunction "2_P$2") (pintype "passive"))
      (node (ref "C49") (pin "P$2") (pinfunction "2_P$2") (pintype "passive"))
      (node (ref "C5") (pin "P$2") (pinfunction "2_P$2") (pintype "passive"))
      (node (ref "C50") (pin "P$2") (pinfunction "2_P$2") (pintype "passive"))
      (node (ref "C51") (pin "P$2") (pinfunction "2_P$2") (pintype "passive"))
      (node (ref "C52") (pin "P$2") (pinfunction "2_P$2") (pintype "passive"))
      (node (ref "C53") (pin "P$2") (pinfunction "2_P$2") (pintype "passive"))
      (node (ref "C54") (pin "P$1") (pinfunction "1_P$1") (pintype "passive"))
      (node (ref "C55") (pin "P$1") (pinfunction "1_P$1") (pintype "passive"))
      (node (ref "C56") (pin "P$1") (pinfunction "1_P$1") (pintype "passive"))
      (node (ref "C57") (pin "P$2") (pinfunction "2_P$2") (pintype "passive"))
      (node (ref "C58") (pin "P$2") (pinfunction "2_P$2") (pintype "passive"))
      (node (ref "C59") (pin "P$2") (pinfunction "2_P$2") (pintype "passive"))
      (node (ref "C60") (pin "P$2") (pinfunction "2_P$2") (pintype "passive"))
      (node (ref "C61") (pin "P$1") (pinfunction "1_P$1") (pintype "passive"))
      (node (ref "C8") (pin "P$2") (pinfunction "2_P$2") (pintype "passive"))
      (node (ref "J1") (pin "P$1") (pinfunction "P$1_P$1") (pintype "bidirectional"))
      (node (ref "J10") (pin "P$1") (pinfunction "P$1_P$1") (pintype "bidirectional"))
      (node (ref "J11") (pin "10") (pinfunction "10_10") (pintype "passive"))
      (node (ref "J11") (pin "6") (pinfunction "6_6") (pintype "passive"))
      (node (ref "J11") (pin "8") (pinfunction "8_8") (pintype "passive"))
      (node (ref "J2") (pin "P$5") (pinfunction "GND_P$5") (pintype "bidirectional"))
      (node (ref "J3") (pin "GND") (pinfunction "GND_GND") (pintype "power_in"))
      (node (ref "J4") (pin "10") (pinfunction "GLO_10") (pintype "bidirectional"))
      (node (ref "J4") (pin "8") (pinfunction "P8_8") (pintype "bidirectional"))
      (node (ref "J6") (pin "10") (pinfunction "10_10") (pintype "passive"))
      (node (ref "J6") (pin "2") (pinfunction "2_2") (pintype "passive"))
      (node (ref "J6") (pin "4") (pinfunction "4_4") (pintype "passive"))
      (node (ref "J6") (pin "6") (pinfunction "6_6") (pintype "passive"))
      (node (ref "J6") (pin "8") (pinfunction "8_8") (pintype "passive"))
      (node (ref "J9") (pin "6") (pinfunction "SUPPLY_VOLTAGE_GROUND_6") (pintype "power_in"))
      (node (ref "LED3") (pin "2") (pinfunction "C_2") (pintype "passive"))
      (node (ref "R16") (pin "P$1") (pinfunction "1_P$1") (pintype "passive"))
      (node (ref "R17") (pin "P$1") (pinfunction "1_P$1") (pintype "passive"))
      (node (ref "R19") (pin "P$1") (pinfunction "1_P$1") (pintype "passive"))
      (node (ref "R25") (pin "P$1") (pinfunction "1_P$1") (pintype "passive"))
      (node (ref "R7") (pin "P$1") (pinfunction "1_P$1") (pintype "passive"))
      (node (ref "U$4") (pin "P$2") (pinfunction "2_P$2") (pintype "passive"))
      (node (ref "U2") (pin "2") (pinfunction "GND_2") (pintype "input"))
      (node (ref "U3") (pin "22") (pinfunction "GND_22") (pintype "power_in"))
      (node (ref "U3") (pin "25") (pinfunction "25_25") (pintype "passive"))
      (node (ref "U4") (pin "111") (pinfunction "VSS(IO)5_111") (pintype "bidirectional"))
      (node (ref "U4") (pin "124") (pinfunction "VSS(IO)6_124") (pintype "bidirectional"))
      (node (ref "U4") (pin "139") (pinfunction "VSS(IO)7_139") (pintype "bidirectional"))
      (node (ref "U4") (pin "150") (pinfunction "VSS(IO)8_150") (pintype "bidirectional"))
      (node (ref "U4") (pin "153") (pinfunction "VREFL_153") (pintype "bidirectional"))
      (node (ref "U4") (pin "156") (pinfunction "AVSS0_156") (pintype "bidirectional"))
      (node (ref "U4") (pin "157") (pinfunction "VREFL0_157") (pintype "bidirectional"))
      (node (ref "U4") (pin "170") (pinfunction "VSS(IO)9_170") (pintype "bidirectional"))
      (node (ref "U4") (pin "22") (pinfunction "VSS1_22") (pintype "bidirectional"))
      (node (ref "U4") (pin "28") (pinfunction "AVSS_USBHS_28") (pintype "bidirectional"))
      (node (ref "U4") (pin "29") (pinfunction "PVSS_USBHS_29") (pintype "bidirectional"))
      (node (ref "U4") (pin "30") (pinfunction "VSS2_USBHS_30") (pintype "bidirectional"))
      (node (ref "U4") (pin "33") (pinfunction "VSS1_USBHS_33") (pintype "bidirectional"))
      (node (ref "U4") (pin "35") (pinfunction "VSSIO_35") (pintype "bidirectional"))
      (node (ref "U4") (pin "45") (pinfunction "VSS_USB_45") (pintype "bidirectional"))
      (node (ref "U4") (pin "60") (pinfunction "VSS(IO)2_60") (pintype "bidirectional"))
      (node (ref "U4") (pin "63") (pinfunction "VSS(IO/DCDC)_63") (pintype "bidirectional"))
      (node (ref "U4") (pin "66") (pinfunction "VCC_DCDC(IO/DCDC)_66") (pintype "bidirectional"))
      (node (ref "U4") (pin "83") (pinfunction "VSS(IO)3_83") (pintype "bidirectional"))
      (node (ref "U4") (pin "98") (pinfunction "VSS(IO)4_98") (pintype "bidirectional"))
      (node (ref "U5") (pin "2") (pinfunction "2_2") (pintype "bidirectional"))
      (node (ref "U5") (pin "4") (pinfunction "4_4") (pintype "bidirectional"))
      (node (ref "X4") (pin "2") (pinfunction "2_2") (pintype "bidirectional"))
      (node (ref "X4") (pin "4") (pinfunction "4_4") (pintype "bidirectional"))
    )
    (net (code "17") (name "GNDE") (class "Default")
      (node (ref "J1") (pin "P$4") (pinfunction "P$4_P$4") (pintype "bidirectional"))
      (node (ref "J2") (pin "P$6") (pinfunction "SHIELD1_P$6") (pintype "bidirectional"))
      (node (ref "J2") (pin "P$7") (pinfunction "SHIELD2_P$7") (pintype "bidirectional"))
      (node (ref "J2") (pin "P$8") (pinfunction "SHIELD3_P$8") (pintype "bidirectional"))
      (node (ref "J2") (pin "P$9") (pinfunction "SHIELD4_P$9") (pintype "bidirectional"))
      (node (ref "J3") (pin "SHLD1") (pinfunction "SHIELD_1_SHLD1") (pintype "bidirectional"))
      (node (ref "J3") (pin "SHLD2") (pinfunction "SHIELD_2_SHLD2") (pintype "bidirectional"))
      (node (ref "J4") (pin "13") (pinfunction "GNDE0_13") (pintype "bidirectional"))
      (node (ref "J4") (pin "14") (pinfunction "GNDE1_14") (pintype "bidirectional"))
      (node (ref "J9") (pin "S1") (pinfunction "SHIELD_S1") (pintype "passive"))
      (node (ref "J9") (pin "S2") (pinfunction "SHIELD_S2") (pintype "passive"))
      (node (ref "J9") (pin "S3") (pinfunction "SHIELD_S3") (pintype "passive"))
      (node (ref "J9") (pin "S4") (pinfunction "SHIELD_S4") (pintype "passive"))
    )
    (net (code "18") (name "ID") (class "Default")
      (node (ref "J2") (pin "P$4") (pinfunction "ID_P$4") (pintype "bidirectional"))
    )
    (net (code "19") (name "IIC_1_SCL") (class "Default")
      (node (ref "J10") (pin "P$5") (pinfunction "P$5_P$5") (pintype "bidirectional"))
      (node (ref "R20") (pin "P$2") (pinfunction "2_P$2") (pintype "passive"))
      (node (ref "U4") (pin "132") (pinfunction "P1_0_132") (pintype "bidirectional"))
    )
    (net (code "20") (name "IIC_1_SDA") (class "Default")
      (node (ref "J10") (pin "P$6") (pinfunction "P$6_P$6") (pintype "bidirectional"))
      (node (ref "R21") (pin "P$2") (pinfunction "2_P$2") (pintype "passive"))
      (node (ref "U4") (pin "131") (pinfunction "P1_1_131") (pintype "bidirectional"))
    )
    (net (code "21") (name "INT_MI_01") (class "Default")
      (node (ref "J10") (pin "P$39") (pinfunction "P$39_P$39") (pintype "bidirectional"))
      (node (ref "U4") (pin "87") (pinfunction "P3_1_87") (pintype "bidirectional"))
    )
    (net (code "22") (name "INT_MI_02") (class "Default")
      (node (ref "J10") (pin "P$40") (pinfunction "P$40_P$40") (pintype "bidirectional"))
      (node (ref "U4") (pin "86") (pinfunction "P3_2_86") (pintype "bidirectional"))
    )
    (net (code "23") (name "INT_MI_03") (class "Default")
      (node (ref "J10") (pin "P$9") (pinfunction "P$9_P$9") (pintype "bidirectional"))
      (node (ref "U4") (pin "128") (pinfunction "P1_4_128") (pintype "bidirectional"))
    )
    (net (code "24") (name "INT_MI_04") (class "Default")
      (node (ref "J10") (pin "P$10") (pinfunction "P$10_P$10") (pintype "bidirectional"))
      (node (ref "U4") (pin "127") (pinfunction "P1_5_127") (pintype "bidirectional"))
    )
    (net (code "25") (name "LED1{slash}SPEED") (class "Default")
      (node (ref "J4") (pin "11") (pinfunction "YLO_11") (pintype "bidirectional"))
      (node (ref "U3") (pin "23") (pinfunction "LED0/ANEN_SPEED_23") (pintype "bidirectional"))
    )
    (net (code "26") (name "NC") (class "Default")
      (node (ref "J4") (pin "7") (pinfunction "P7_7") (pintype "bidirectional"))
    )
    (net (code "27") (name "Net-(C16-1)") (class "Default")
      (node (ref "C16") (pin "P$1") (pinfunction "1_P$1") (pintype "passive"))
      (node (ref "J2") (pin "P$1") (pinfunction "VBUS_P$1") (pintype "bidirectional"))
      (node (ref "R4") (pin "P$2") (pinfunction "2_P$2") (pintype "passive"))
      (node (ref "R7") (pin "P$2") (pinfunction "2_P$2") (pintype "passive"))
    )
    (net (code "28") (name "Net-(C31-1)") (class "Default")
      (node (ref "C31") (pin "P$1") (pinfunction "1_P$1") (pintype "passive"))
      (node (ref "U4") (pin "62") (pinfunction "VCL1_62") (pintype "bidirectional"))
    )
    (net (code "29") (name "Net-(C37-2)") (class "Default")
      (node (ref "C37") (pin "P$2") (pinfunction "2_P$2") (pintype "passive"))
      (node (ref "U4") (pin "148") (pinfunction "VCL2_148") (pintype "bidirectional"))
    )
    (net (code "30") (name "Net-(C38-1)") (class "Default")
      (node (ref "C38") (pin "P$1") (pinfunction "1_P$1") (pintype "passive"))
      (node (ref "U4") (pin "19") (pinfunction "VCLO_19") (pintype "bidirectional"))
    )
    (net (code "31") (name "Net-(C43-1)") (class "Default")
      (node (ref "C43") (pin "P$1") (pinfunction "1_P$1") (pintype "passive"))
      (node (ref "C44") (pin "P$1") (pinfunction "1_P$1") (pintype "passive"))
      (node (ref "FB2/2") (pin "2") (pinfunction "P$2_2") (pintype "bidirectional"))
      (node (ref "U3") (pin "2") (pinfunction "VDDA_3.3_2") (pintype "power_in"))
    )
    (net (code "32") (name "Net-(J2-D+)") (class "Default")
      (node (ref "J2") (pin "P$3") (pinfunction "D+_P$3") (pintype "bidirectional"))
      (node (ref "R6") (pin "P$2") (pinfunction "2_P$2") (pintype "passive"))
    )
    (net (code "33") (name "Net-(J2-D-)") (class "Default")
      (node (ref "J2") (pin "P$2") (pinfunction "D-_P$2") (pintype "bidirectional"))
      (node (ref "R5") (pin "P$2") (pinfunction "2_P$2") (pintype "passive"))
    )
    (net (code "34") (name "Net-(LED3-A)") (class "Default")
      (node (ref "LED3") (pin "1") (pinfunction "A_1") (pintype "passive"))
      (node (ref "R13") (pin "P$1") (pinfunction "1_P$1") (pintype "passive"))
    )
    (net (code "35") (name "Net-(R16-2)") (class "Default")
      (node (ref "R16") (pin "P$2") (pinfunction "2_P$2") (pintype "passive"))
      (node (ref "U4") (pin "65") (pinfunction "VLO2(DCDC)_65") (pintype "bidirectional"))
    )
    (net (code "36") (name "Net-(R17-2)") (class "Default")
      (node (ref "R17") (pin "P$2") (pinfunction "2_P$2") (pintype "passive"))
      (node (ref "U4") (pin "64") (pinfunction "VLO1(DCDC)_64") (pintype "bidirectional"))
    )
    (net (code "37") (name "Net-(R19-2)") (class "Default")
      (node (ref "R19") (pin "P$2") (pinfunction "2_P$2") (pintype "passive"))
      (node (ref "U4") (pin "27") (pinfunction "USBHS_RREF_27") (pintype "bidirectional"))
    )
    (net (code "38") (name "P0_00") (class "Default")
      (node (ref "J5") (pin "P$2") (pinfunction "P$2_P$2") (pintype "bidirectional"))
      (node (ref "U4") (pin "169") (pinfunction "P0_0/AN0\\00_169") (pintype "bidirectional"))
    )
    (net (code "39") (name "P0_01") (class "Default")
      (node (ref "J5") (pin "P$1") (pinfunction "P$1_P$1") (pintype "bidirectional"))
      (node (ref "U4") (pin "168") (pinfunction "P0_1/AN001_168") (pintype "bidirectional"))
    )
    (net (code "40") (name "P0_02") (class "Default")
      (node (ref "J12") (pin "1") (pinfunction "1_1") (pintype "passive"))
      (node (ref "U4") (pin "167") (pinfunction "P0_2/AN002_167") (pintype "bidirectional"))
    )
    (net (code "41") (name "P0_03") (class "Default")
      (node (ref "J12") (pin "3") (pinfunction "3_3") (pintype "passive"))
      (node (ref "U4") (pin "166") (pinfunction "P0_3/PGAVSS000_166") (pintype "bidirectional"))
    )
    (net (code "42") (name "P0_04") (class "Default")
      (node (ref "J12") (pin "5") (pinfunction "5_5") (pintype "passive"))
      (node (ref "U4") (pin "165") (pinfunction "P0_4/AN100_165") (pintype "bidirectional"))
    )
    (net (code "43") (name "P0_05") (class "Default")
      (node (ref "J12") (pin "7") (pinfunction "7_7") (pintype "passive"))
      (node (ref "U4") (pin "164") (pinfunction "P0_5/AN101_164") (pintype "bidirectional"))
    )
    (net (code "44") (name "P0_06") (class "Default")
      (node (ref "J12") (pin "9") (pinfunction "9_9") (pintype "passive"))
      (node (ref "U4") (pin "163") (pinfunction "P0_6/AN102_163") (pintype "bidirectional"))
    )
    (net (code "45") (name "P0_07") (class "Default")
      (node (ref "J12") (pin "10") (pinfunction "10_10") (pintype "passive"))
      (node (ref "U4") (pin "162") (pinfunction "P0_7/PGVSS100_162") (pintype "bidirectional"))
    )
    (net (code "46") (name "P0_08") (class "Default")
      (node (ref "J12") (pin "8") (pinfunction "8_8") (pintype "passive"))
      (node (ref "U4") (pin "161") (pinfunction "P0_8/AN003_161") (pintype "bidirectional"))
    )
    (net (code "47") (name "P0_09") (class "Default")
      (node (ref "J12") (pin "6") (pinfunction "6_6") (pintype "passive"))
      (node (ref "U4") (pin "160") (pinfunction "P0_9/AN004_160") (pintype "bidirectional"))
    )
    (net (code "48") (name "P0_14") (class "Default")
      (node (ref "J12") (pin "4") (pinfunction "4_4") (pintype "passive"))
      (node (ref "U4") (pin "152") (pinfunction "P0_14/DA0/AN005/AN105_152") (pintype "bidirectional"))
    )
    (net (code "49") (name "P0_15") (class "Default")
      (node (ref "J12") (pin "2") (pinfunction "2_2") (pintype "passive"))
      (node (ref "U4") (pin "151") (pinfunction "P0_15/DA1/AN006/AN106_151") (pintype "bidirectional"))
    )
    (net (code "50") (name "P1_02") (class "Default")
      (node (ref "J10") (pin "P$7") (pinfunction "P$7_P$7") (pintype "bidirectional"))
      (node (ref "U4") (pin "130") (pinfunction "P1_2_130") (pintype "bidirectional"))
    )
    (net (code "51") (name "P1_03") (class "Default")
      (node (ref "J10") (pin "P$8") (pinfunction "P$8_P$8") (pintype "bidirectional"))
      (node (ref "U4") (pin "129") (pinfunction "P1_3_129") (pintype "bidirectional"))
    )
    (net (code "52") (name "P1_06") (class "Default")
      (node (ref "J10") (pin "P$11") (pinfunction "P$11_P$11") (pintype "bidirectional"))
      (node (ref "U4") (pin "126") (pinfunction "P1_6_126") (pintype "bidirectional"))
    )
    (net (code "53") (name "P1_07") (class "Default")
      (node (ref "J10") (pin "P$12") (pinfunction "P$12_P$12") (pintype "bidirectional"))
      (node (ref "U4") (pin "125") (pinfunction "P1_7_125") (pintype "bidirectional"))
    )
    (net (code "54") (name "P1_11") (class "Default")
      (node (ref "J10") (pin "P$38") (pinfunction "P$38_P$38") (pintype "bidirectional"))
      (node (ref "U4") (pin "92") (pinfunction "P1_11_92") (pintype "bidirectional"))
    )
    (net (code "55") (name "P1_12") (class "Default")
      (node (ref "J10") (pin "P$37") (pinfunction "P$37_P$37") (pintype "bidirectional"))
      (node (ref "U4") (pin "93") (pinfunction "P1_12_93") (pintype "bidirectional"))
    )
    (net (code "56") (name "P1_13") (class "Default")
      (node (ref "J10") (pin "P$36") (pinfunction "P$36_P$36") (pintype "bidirectional"))
      (node (ref "U4") (pin "94") (pinfunction "P1_13_94") (pintype "bidirectional"))
    )
    (net (code "57") (name "P1_14") (class "Default")
      (node (ref "J10") (pin "P$35") (pinfunction "P$35_P$35") (pintype "bidirectional"))
      (node (ref "U4") (pin "95") (pinfunction "P1_14_95") (pintype "bidirectional"))
    )
    (net (code "58") (name "P1_15") (class "Default")
      (node (ref "J10") (pin "P$34") (pinfunction "P$34_P$34") (pintype "bidirectional"))
      (node (ref "U4") (pin "96") (pinfunction "P1_15_96") (pintype "bidirectional"))
    )
    (net (code "59") (name "P2_00") (class "Default")
      (node (ref "J7") (pin "P$13") (pinfunction "P$13_P$13") (pintype "bidirectional"))
      (node (ref "U4") (pin "69") (pinfunction "P2_0(INPUT_ONLY)_69") (pintype "bidirectional"))
    )
    (net (code "60") (name "P2_01") (class "Default")
      (node (ref "J7") (pin "P$14") (pinfunction "P$14_P$14") (pintype "bidirectional"))
      (node (ref "U4") (pin "68") (pinfunction "P2_1/MD_68") (pintype "bidirectional"))
    )
    (net (code "61") (name "P2_02") (class "Default")
      (node (ref "J7") (pin "P$19") (pinfunction "P$19_P$19") (pintype "bidirectional"))
      (node (ref "U4") (pin "54") (pinfunction "P2_2_54") (pintype "bidirectional"))
    )
    (net (code "62") (name "P2_03") (class "Default")
      (node (ref "J6") (pin "1") (pinfunction "1_1") (pintype "passive"))
      (node (ref "U4") (pin "53") (pinfunction "P2_3_53") (pintype "bidirectional"))
    )
    (net (code "63") (name "P2_04") (class "Default")
      (node (ref "J6") (pin "3") (pinfunction "3_3") (pintype "passive"))
      (node (ref "U4") (pin "52") (pinfunction "P2_4_52") (pintype "bidirectional"))
    )
    (net (code "64") (name "P2_05") (class "Default")
      (node (ref "J6") (pin "5") (pinfunction "5_5") (pintype "passive"))
      (node (ref "U4") (pin "51") (pinfunction "P2_5_51") (pintype "bidirectional"))
    )
    (net (code "65") (name "P2_06") (class "Default")
      (node (ref "J6") (pin "7") (pinfunction "7_7") (pintype "passive"))
      (node (ref "U4") (pin "50") (pinfunction "P2_6_50") (pintype "bidirectional"))
    )
    (net (code "66") (name "P2_07") (class "Default")
      (node (ref "J6") (pin "9") (pinfunction "9_9") (pintype "passive"))
      (node (ref "U4") (pin "49") (pinfunction "P2_7_49") (pintype "bidirectional"))
    )
    (net (code "67") (name "P3_03") (class "Default")
      (node (ref "J7") (pin "P$2") (pinfunction "P$2_P$2") (pintype "bidirectional"))
      (node (ref "U4") (pin "85") (pinfunction "P3_3_85") (pintype "bidirectional"))
    )
    (net (code "68") (name "P3_04") (class "Default")
      (node (ref "J7") (pin "P$4") (pinfunction "P$4_P$4") (pintype "bidirectional"))
      (node (ref "U4") (pin "82") (pinfunction "P3_4_82") (pintype "bidirectional"))
    )
    (net (code "69") (name "P3_05") (class "Default")
      (node (ref "J7") (pin "P$6") (pinfunction "P$6_P$6") (pintype "bidirectional"))
      (node (ref "U4") (pin "81") (pinfunction "P3_5_81") (pintype "bidirectional"))
    )
    (net (code "70") (name "P3_06") (class "Default")
      (node (ref "J7") (pin "P$1") (pinfunction "P$1_P$1") (pintype "bidirectional"))
      (node (ref "U4") (pin "80") (pinfunction "P3_6_80") (pintype "bidirectional"))
    )
    (net (code "71") (name "P3_07") (class "Default")
      (node (ref "J7") (pin "P$3") (pinfunction "P$3_P$3") (pintype "bidirectional"))
      (node (ref "U4") (pin "79") (pinfunction "P3_7_79") (pintype "bidirectional"))
    )
    (net (code "72") (name "P3_09") (class "Default")
      (node (ref "J7") (pin "P$5") (pinfunction "P$5_P$5") (pintype "bidirectional"))
      (node (ref "U4") (pin "77") (pinfunction "P3_9_77") (pintype "bidirectional"))
    )
    (net (code "73") (name "P3_10") (class "Default")
      (node (ref "J7") (pin "P$7") (pinfunction "P$7_P$7") (pintype "bidirectional"))
      (node (ref "U4") (pin "76") (pinfunction "P3_10_76") (pintype "bidirectional"))
    )
    (net (code "74") (name "P3_11") (class "Default")
      (node (ref "J7") (pin "P$8") (pinfunction "P$8_P$8") (pintype "bidirectional"))
      (node (ref "U4") (pin "75") (pinfunction "P3_11_75") (pintype "bidirectional"))
    )
    (net (code "75") (name "P3_12") (class "Default")
      (node (ref "J7") (pin "P$9") (pinfunction "P$9_P$9") (pintype "bidirectional"))
      (node (ref "U4") (pin "74") (pinfunction "P3_12_74") (pintype "bidirectional"))
    )
    (net (code "76") (name "P3_13") (class "Default")
      (node (ref "J7") (pin "P$20") (pinfunction "P$20_P$20") (pintype "bidirectional"))
      (node (ref "U4") (pin "55") (pinfunction "P3_13_55") (pintype "bidirectional"))
    )
    (net (code "77") (name "P3_14") (class "Default")
      (node (ref "J7") (pin "P$17") (pinfunction "P$17_P$17") (pintype "bidirectional"))
      (node (ref "U4") (pin "56") (pinfunction "P3_14_56") (pintype "bidirectional"))
    )
    (net (code "78") (name "P3_15") (class "Default")
      (node (ref "J7") (pin "P$18") (pinfunction "P$18_P$18") (pintype "bidirectional"))
      (node (ref "U4") (pin "57") (pinfunction "P3_15_57") (pintype "bidirectional"))
    )
    (net (code "79") (name "P4_00") (class "Default")
      (node (ref "J5") (pin "P$7") (pinfunction "P$7_P$7") (pintype "bidirectional"))
      (node (ref "U4") (pin "1") (pinfunction "P4_0_1") (pintype "bidirectional"))
    )
    (net (code "80") (name "P4_01") (class "Default")
      (node (ref "J5") (pin "P$8") (pinfunction "P$8_P$8") (pintype "bidirectional"))
      (node (ref "U4") (pin "2") (pinfunction "P4_1_2") (pintype "bidirectional"))
    )
    (net (code "81") (name "P4_02") (class "Default")
      (node (ref "J5") (pin "P$9") (pinfunction "P$9_P$9") (pintype "bidirectional"))
      (node (ref "U4") (pin "3") (pinfunction "P4_2_3") (pintype "bidirectional"))
    )
    (net (code "82") (name "P4_08") (class "Default")
      (node (ref "J5") (pin "P$20") (pinfunction "P$20_P$20") (pintype "bidirectional"))
      (node (ref "U4") (pin "43") (pinfunction "P4_8_43") (pintype "bidirectional"))
    )
    (net (code "83") (name "P4_09") (class "Default")
      (node (ref "J5") (pin "P$19") (pinfunction "P$19_P$19") (pintype "bidirectional"))
      (node (ref "U4") (pin "42") (pinfunction "P4_9_42") (pintype "bidirectional"))
    )
    (net (code "84") (name "P4_10") (class "Default")
      (node (ref "J5") (pin "P$18") (pinfunction "P$18_P$18") (pintype "bidirectional"))
      (node (ref "U4") (pin "41") (pinfunction "P4_10_41") (pintype "bidirectional"))
    )
    (net (code "85") (name "P4_11") (class "Default")
      (node (ref "J5") (pin "P$17") (pinfunction "P$17_P$17") (pintype "bidirectional"))
      (node (ref "U4") (pin "40") (pinfunction "P4_11_40") (pintype "bidirectional"))
    )
    (net (code "86") (name "P4_12") (class "Default")
      (node (ref "J5") (pin "P$16") (pinfunction "P$16_P$16") (pintype "bidirectional"))
      (node (ref "U4") (pin "39") (pinfunction "P4_12_39") (pintype "bidirectional"))
    )
    (net (code "87") (name "P4_13") (class "Default")
      (node (ref "J5") (pin "P$15") (pinfunction "P$15_P$15") (pintype "bidirectional"))
      (node (ref "U4") (pin "38") (pinfunction "P4_13_38") (pintype "bidirectional"))
    )
    (net (code "88") (name "P4_14") (class "Default")
      (node (ref "J5") (pin "P$14") (pinfunction "P$14_P$14") (pintype "bidirectional"))
      (node (ref "U4") (pin "37") (pinfunction "P4_14_37") (pintype "bidirectional"))
    )
    (net (code "89") (name "P4_15") (class "Default")
      (node (ref "J5") (pin "P$13") (pinfunction "P$13_P$13") (pintype "bidirectional"))
      (node (ref "U4") (pin "36") (pinfunction "P4_15_36") (pintype "bidirectional"))
    )
    (net (code "90") (name "P5_11") (class "Default")
      (node (ref "J5") (pin "P$6") (pinfunction "P$6_P$6") (pintype "bidirectional"))
      (node (ref "U4") (pin "176") (pinfunction "P5_11_176") (pintype "bidirectional"))
    )
    (net (code "91") (name "P5_12") (class "Default")
      (node (ref "J5") (pin "P$5") (pinfunction "P$5_P$5") (pintype "bidirectional"))
      (node (ref "U4") (pin "175") (pinfunction "P5_12_175") (pintype "bidirectional"))
    )
    (net (code "92") (name "P5_13") (class "Default")
      (node (ref "J5") (pin "P$4") (pinfunction "P$4_P$4") (pintype "bidirectional"))
      (node (ref "U4") (pin "174") (pinfunction "P5_13_174") (pintype "bidirectional"))
    )
    (net (code "93") (name "P6_00") (class "Default")
      (node (ref "J10") (pin "P$13") (pinfunction "P$13_P$13") (pintype "bidirectional"))
      (node (ref "U4") (pin "122") (pinfunction "P6_0_122") (pintype "bidirectional"))
    )
    (net (code "94") (name "P6_01") (class "Default")
      (node (ref "J10") (pin "P$14") (pinfunction "P$14_P$14") (pintype "bidirectional"))
      (node (ref "U4") (pin "121") (pinfunction "P6_1_121") (pintype "bidirectional"))
    )
    (net (code "95") (name "P6_02") (class "Default")
      (node (ref "J10") (pin "P$15") (pinfunction "P$15_P$15") (pintype "bidirectional"))
      (node (ref "U4") (pin "120") (pinfunction "P6_2_120") (pintype "bidirectional"))
    )
    (net (code "96") (name "P6_03") (class "Default")
      (node (ref "J10") (pin "P$16") (pinfunction "P$16_P$16") (pintype "bidirectional"))
      (node (ref "U4") (pin "119") (pinfunction "P6_3_119") (pintype "bidirectional"))
    )
    (net (code "97") (name "P6_04") (class "Default")
      (node (ref "J10") (pin "P$17") (pinfunction "P$17_P$17") (pintype "bidirectional"))
      (node (ref "U4") (pin "118") (pinfunction "P6_4_118") (pintype "bidirectional"))
    )
    (net (code "98") (name "P6_05") (class "Default")
      (node (ref "J10") (pin "P$18") (pinfunction "P$18_P$18") (pintype "bidirectional"))
      (node (ref "U4") (pin "117") (pinfunction "P6_5_117") (pintype "bidirectional"))
    )
    (net (code "99") (name "P6_06") (class "Default")
      (node (ref "J10") (pin "P$19") (pinfunction "P$19_P$19") (pintype "bidirectional"))
      (node (ref "U4") (pin "116") (pinfunction "P6_6_116") (pintype "bidirectional"))
    )
    (net (code "100") (name "P6_07") (class "Default")
      (node (ref "J10") (pin "P$20") (pinfunction "P$20_P$20") (pintype "bidirectional"))
      (node (ref "U4") (pin "115") (pinfunction "P6_7_115") (pintype "bidirectional"))
    )
    (net (code "101") (name "P6_08") (class "Default")
      (node (ref "J10") (pin "P$33") (pinfunction "P$33_P$33") (pintype "bidirectional"))
      (node (ref "U4") (pin "99") (pinfunction "P6_8_99") (pintype "bidirectional"))
    )
    (net (code "102") (name "P6_09") (class "Default")
      (node (ref "J10") (pin "P$32") (pinfunction "P$32_P$32") (pintype "bidirectional"))
      (node (ref "U4") (pin "100") (pinfunction "P6_9_100") (pintype "bidirectional"))
    )
    (net (code "103") (name "P6_10") (class "Default")
      (node (ref "J10") (pin "P$31") (pinfunction "P$31_P$31") (pintype "bidirectional"))
      (node (ref "U4") (pin "101") (pinfunction "P6_10_101") (pintype "bidirectional"))
    )
    (net (code "104") (name "P6_11") (class "Default")
      (node (ref "J10") (pin "P$30") (pinfunction "P$30_P$30") (pintype "bidirectional"))
      (node (ref "U4") (pin "102") (pinfunction "P6_11_102") (pintype "bidirectional"))
    )
    (net (code "105") (name "P6_12") (class "Default")
      (node (ref "J10") (pin "P$29") (pinfunction "P$29_P$29") (pintype "bidirectional"))
      (node (ref "U4") (pin "103") (pinfunction "P6_12_103") (pintype "bidirectional"))
    )
    (net (code "106") (name "P6_13") (class "Default")
      (node (ref "J10") (pin "P$28") (pinfunction "P$28_P$28") (pintype "bidirectional"))
      (node (ref "U4") (pin "104") (pinfunction "P6_13_104") (pintype "bidirectional"))
    )
    (net (code "107") (name "P6_14") (class "Default")
      (node (ref "J10") (pin "P$27") (pinfunction "P$27_P$27") (pintype "bidirectional"))
      (node (ref "U4") (pin "105") (pinfunction "P6_14_105") (pintype "bidirectional"))
    )
    (net (code "108") (name "P6_15") (class "Default")
      (node (ref "J10") (pin "P$26") (pinfunction "P$26_P$26") (pintype "bidirectional"))
      (node (ref "U4") (pin "106") (pinfunction "P6_15_106") (pintype "bidirectional"))
    )
    (net (code "109") (name "P7_06") (class "Default")
      (node (ref "J5") (pin "P$10") (pinfunction "P$10_P$10") (pintype "bidirectional"))
      (node (ref "U4") (pin "14") (pinfunction "P7_6_14") (pintype "bidirectional"))
    )
    (net (code "110") (name "P7_07") (class "Default")
      (node (ref "J5") (pin "P$11") (pinfunction "P$11_P$11") (pintype "bidirectional"))
      (node (ref "U4") (pin "15") (pinfunction "P7_7_15") (pintype "bidirectional"))
    )
    (net (code "111") (name "P8_00") (class "Default")
      (node (ref "J10") (pin "P$4") (pinfunction "P$4_P$4") (pintype "bidirectional"))
      (node (ref "U4") (pin "133") (pinfunction "P8_0_133") (pintype "bidirectional"))
    )
    (net (code "112") (name "P8_01") (class "Default")
      (node (ref "J10") (pin "P$3") (pinfunction "P$3_P$3") (pintype "bidirectional"))
      (node (ref "U4") (pin "134") (pinfunction "P8_1_134") (pintype "bidirectional"))
    )
    (net (code "113") (name "P8_02") (class "Default")
      (node (ref "J10") (pin "P$2") (pinfunction "P$2_P$2") (pintype "bidirectional"))
      (node (ref "U4") (pin "135") (pinfunction "P8_2_135") (pintype "bidirectional"))
    )
    (net (code "114") (name "P8_03") (class "Default")
      (node (ref "U4") (pin "136") (pinfunction "P8_3_136") (pintype "bidirectional"))
    )
    (net (code "115") (name "P8_04") (class "Default")
      (node (ref "U4") (pin "137") (pinfunction "P8_4_137") (pintype "bidirectional"))
    )
    (net (code "116") (name "P8_05") (class "Default")
      (node (ref "J5") (pin "P$3") (pinfunction "P$3_P$3") (pintype "bidirectional"))
      (node (ref "U4") (pin "173") (pinfunction "P8_5_173") (pintype "bidirectional"))
    )
    (net (code "117") (name "P9_00") (class "Default")
      (node (ref "J7") (pin "P$16") (pinfunction "P$16_P$16") (pintype "bidirectional"))
      (node (ref "U4") (pin "58") (pinfunction "P9_0_58") (pintype "bidirectional"))
    )
    (net (code "118") (name "P9_01") (class "Default")
      (node (ref "J7") (pin "P$15") (pinfunction "P$15_P$15") (pintype "bidirectional"))
      (node (ref "U4") (pin "59") (pinfunction "P9_1_59") (pintype "bidirectional"))
    )
    (net (code "119") (name "P9_05") (class "Default")
      (node (ref "J7") (pin "P$10") (pinfunction "P$10_P$10") (pintype "bidirectional"))
      (node (ref "U4") (pin "73") (pinfunction "P9_5_73") (pintype "bidirectional"))
    )
    (net (code "120") (name "P9_06") (class "Default")
      (node (ref "J7") (pin "P$11") (pinfunction "P$11_P$11") (pintype "bidirectional"))
      (node (ref "U4") (pin "72") (pinfunction "P9_6_72") (pintype "bidirectional"))
    )
    (net (code "121") (name "P9_07") (class "Default")
      (node (ref "J7") (pin "P$12") (pinfunction "P$12_P$12") (pintype "bidirectional"))
      (node (ref "U4") (pin "71") (pinfunction "P9_7_71") (pintype "bidirectional"))
    )
    (net (code "122") (name "P9_08") (class "Default")
      (node (ref "U4") (pin "70") (pinfunction "P9_8_70") (pintype "bidirectional"))
    )
    (net (code "123") (name "PA_00") (class "Default")
      (node (ref "J10") (pin "P$21") (pinfunction "P$21_P$21") (pintype "bidirectional"))
      (node (ref "U4") (pin "114") (pinfunction "PA_0_114") (pintype "bidirectional"))
    )
    (net (code "124") (name "PA_01") (class "Default")
      (node (ref "J10") (pin "P$22") (pinfunction "P$22_P$22") (pintype "bidirectional"))
      (node (ref "U4") (pin "113") (pinfunction "PA_1_113") (pintype "bidirectional"))
    )
    (net (code "125") (name "PA_08") (class "Default")
      (node (ref "J10") (pin "P$25") (pinfunction "P$25_P$25") (pintype "bidirectional"))
      (node (ref "U4") (pin "107") (pinfunction "PA_8_107") (pintype "bidirectional"))
    )
    (net (code "126") (name "PA_09") (class "Default")
      (node (ref "J10") (pin "P$24") (pinfunction "P$24_P$24") (pintype "bidirectional"))
      (node (ref "U4") (pin "108") (pinfunction "PA_9_108") (pintype "bidirectional"))
    )
    (net (code "127") (name "PA_10") (class "Default")
      (node (ref "J10") (pin "P$23") (pinfunction "P$23_P$23") (pintype "bidirectional"))
      (node (ref "U4") (pin "109") (pinfunction "PA_10_109") (pintype "bidirectional"))
    )
    (net (code "128") (name "PB_00") (class "Default")
      (node (ref "J5") (pin "P$12") (pinfunction "P$12_P$12") (pintype "bidirectional"))
      (node (ref "U4") (pin "16") (pinfunction "PB_0_16") (pintype "bidirectional"))
    )
    (net (code "129") (name "R51") (class "Default")
      (node (ref "J4") (pin "12") (pinfunction "YHI_12") (pintype "bidirectional"))
      (node (ref "R23") (pin "P$1") (pinfunction "1_P$1") (pintype "passive"))
    )
    (net (code "130") (name "R52") (class "Default")
      (node (ref "J4") (pin "9") (pinfunction "GHI_9") (pintype "bidirectional"))
      (node (ref "R24") (pin "P$1") (pinfunction "1_P$1") (pintype "passive"))
    )
    (net (code "131") (name "RESET") (class "Default")
      (node (ref "C57") (pin "P$1") (pinfunction "1_P$1") (pintype "passive"))
      (node (ref "J11") (pin "9") (pinfunction "9_9") (pintype "passive"))
      (node (ref "R18") (pin "P$1") (pinfunction "1_P$1") (pintype "passive"))
      (node (ref "U4") (pin "67") (pinfunction "RES#_67") (pintype "bidirectional"))
    )
    (net (code "132") (name "REXT") (class "Default")
      (node (ref "C47") (pin "P$1") (pinfunction "1_P$1") (pintype "passive"))
      (node (ref "R25") (pin "P$2") (pinfunction "2_P$2") (pintype "passive"))
      (node (ref "U3") (pin "9") (pinfunction "REXT_9") (pintype "input"))
    )
    (net (code "133") (name "RXD0") (class "Default")
      (node (ref "R31") (pin "P$2") (pinfunction "2_P$2") (pintype "passive"))
      (node (ref "U3") (pin "13") (pinfunction "RXD0_13") (pintype "bidirectional"))
    )
    (net (code "134") (name "RXD1") (class "Default")
      (node (ref "R30") (pin "P$2") (pinfunction "2_P$2") (pintype "passive"))
      (node (ref "U3") (pin "12") (pinfunction "RXD1_12") (pintype "bidirectional"))
    )
    (net (code "135") (name "RXER") (class "Default")
      (node (ref "R32") (pin "P$2") (pinfunction "2_P$2") (pintype "passive"))
      (node (ref "U3") (pin "17") (pinfunction "RXER_17") (pintype "bidirectional"))
    )
    (net (code "136") (name "RXM") (class "Default")
      (node (ref "J4") (pin "6") (pinfunction "RD-_6") (pintype "bidirectional"))
      (node (ref "U3") (pin "3") (pinfunction "RXM_3") (pintype "bidirectional"))
    )
    (net (code "137") (name "RXP") (class "Default")
      (node (ref "J4") (pin "3") (pinfunction "RD+_3") (pintype "bidirectional"))
      (node (ref "U3") (pin "4") (pinfunction "RXP_4") (pintype "bidirectional"))
    )
    (net (code "138") (name "SD1_CD") (class "Default")
      (node (ref "J9") (pin "10") (pinfunction "CD_SWITCH2_10") (pintype "bidirectional"))
      (node (ref "U4") (pin "146") (pinfunction "P5_6/AN019_146") (pintype "bidirectional"))
    )
    (net (code "139") (name "SD1_CLK") (class "Default")
      (node (ref "J9") (pin "5") (pinfunction "CLOCK_5") (pintype "bidirectional"))
      (node (ref "U4") (pin "140") (pinfunction "P5_0/AN016_140") (pintype "bidirectional"))
    )
    (net (code "140") (name "SD1_CMD") (class "Default")
      (node (ref "J9") (pin "3") (pinfunction "COMMAND/RESPONSE_3") (pintype "bidirectional"))
      (node (ref "U4") (pin "141") (pinfunction "P5_1/AN116_141") (pintype "bidirectional"))
    )
    (net (code "141") (name "SD1_DAT0") (class "Default")
      (node (ref "J9") (pin "7") (pinfunction "DATA_LINE[BIT_0]_7") (pintype "bidirectional"))
      (node (ref "U4") (pin "142") (pinfunction "P5_2/AN017_142") (pintype "bidirectional"))
    )
    (net (code "142") (name "SD1_DAT1") (class "Default")
      (node (ref "J9") (pin "8") (pinfunction "DATA_LINE[BIT_1]_8") (pintype "bidirectional"))
      (node (ref "U4") (pin "143") (pinfunction "P5_3/AN117_143") (pintype "bidirectional"))
    )
    (net (code "143") (name "SD1_DAT2") (class "Default")
      (node (ref "J9") (pin "1") (pinfunction "DATA_LINE[BIT_2]_1") (pintype "bidirectional"))
      (node (ref "U4") (pin "144") (pinfunction "P5_4/AN018_144") (pintype "bidirectional"))
    )
    (net (code "144") (name "SD1_DAT3") (class "Default")
      (node (ref "J9") (pin "2") (pinfunction "CARD_DETECT/DATA_LINE[BIT_3]_2") (pintype "bidirectional"))
      (node (ref "U4") (pin "145") (pinfunction "P5_5/AN118_145") (pintype "bidirectional"))
    )
    (net (code "145") (name "SD1_WP") (class "Default")
      (node (ref "J9") (pin "9") (pinfunction "CD_SWITCH1_9") (pintype "bidirectional"))
      (node (ref "U4") (pin "147") (pinfunction "P5_7/AN119_147") (pintype "bidirectional"))
    )
    (net (code "146") (name "TCK") (class "Default")
      (node (ref "J11") (pin "7") (pinfunction "7_7") (pintype "passive"))
      (node (ref "U4") (pin "88") (pinfunction "P3_0_88") (pintype "bidirectional"))
    )
    (net (code "147") (name "TDI") (class "Default")
      (node (ref "J11") (pin "1") (pinfunction "1_1") (pintype "passive"))
      (node (ref "U4") (pin "91") (pinfunction "P1_10_91") (pintype "bidirectional"))
    )
    (net (code "148") (name "TDO") (class "Default")
      (node (ref "J11") (pin "3") (pinfunction "3_3") (pintype "passive"))
      (node (ref "U4") (pin "90") (pinfunction "P1_9_90") (pintype "bidirectional"))
    )
    (net (code "149") (name "TMS") (class "Default")
      (node (ref "J11") (pin "5") (pinfunction "5_5") (pintype "passive"))
      (node (ref "U4") (pin "89") (pinfunction "P1_8_89") (pintype "bidirectional"))
    )
    (net (code "150") (name "TXM") (class "Default")
      (node (ref "J4") (pin "2") (pinfunction "TD-_2") (pintype "bidirectional"))
      (node (ref "U3") (pin "5") (pinfunction "TXM_5") (pintype "bidirectional"))
    )
    (net (code "151") (name "TXP") (class "Default")
      (node (ref "J4") (pin "1") (pinfunction "TD+_1") (pintype "bidirectional"))
      (node (ref "U3") (pin "6") (pinfunction "TXP_6") (pintype "bidirectional"))
    )
    (net (code "152") (name "USBHS_FAULT") (class "Default")
      (node (ref "R12") (pin "P$1") (pinfunction "1_P$1") (pintype "passive"))
      (node (ref "U2") (pin "3") (pinfunction "FLG_3") (pintype "input"))
      (node (ref "U4") (pin "78") (pinfunction "P3_8_78") (pintype "bidirectional"))
    )
    (net (code "153") (name "USBHS_N") (class "Default")
      (node (ref "J3") (pin "D-") (pinfunction "D-_D-") (pintype "bidirectional"))
      (node (ref "U4") (pin "31") (pinfunction "USBHS_DM_31") (pintype "bidirectional"))
    )
    (net (code "154") (name "USBHS_P") (class "Default")
      (node (ref "J3") (pin "D+") (pinfunction "D+_D+") (pintype "bidirectional"))
      (node (ref "U4") (pin "32") (pinfunction "USBHS_DP_32") (pintype "bidirectional"))
    )
    (net (code "155") (name "USBHS_VBUS") (class "Default")
      (node (ref "C11") (pin "P$1") (pinfunction "1_P$1") (pintype "passive"))
      (node (ref "C15") (pin "1") (pinfunction "1_1") (pintype "passive"))
      (node (ref "J3") (pin "VBUS") (pinfunction "VBUS_VBUS") (pintype "power_in"))
      (node (ref "U2") (pin "5") (pinfunction "OUT_5") (pintype "input"))
      (node (ref "U4") (pin "17") (pinfunction "PB_1_17") (pintype "bidirectional"))
    )
    (net (code "156") (name "USBHS_VBUSEN") (class "Default")
      (node (ref "R1") (pin "P$1") (pinfunction "1_P$1") (pintype "passive"))
      (node (ref "U2") (pin "1") (pinfunction "EN_1") (pintype "input"))
    )
    (net (code "157") (name "USB_N") (class "Default")
      (node (ref "R5") (pin "P$1") (pinfunction "1_P$1") (pintype "passive"))
      (node (ref "U4") (pin "46") (pinfunction "USB_DM_46") (pintype "bidirectional"))
    )
    (net (code "158") (name "USB_P") (class "Default")
      (node (ref "R6") (pin "P$1") (pinfunction "1_P$1") (pintype "passive"))
      (node (ref "U4") (pin "47") (pinfunction "USB_DP_47") (pintype "bidirectional"))
    )
    (net (code "159") (name "USB_VBUS_B") (class "Default")
      (node (ref "R4") (pin "P$1") (pinfunction "1_P$1") (pintype "passive"))
      (node (ref "U4") (pin "44") (pinfunction "P4_7_44") (pintype "bidirectional"))
    )
    (net (code "160") (name "VCL_F(FLASH)") (class "Default")
      (node (ref "C36") (pin "P$2") (pinfunction "2_P$2") (pintype "passive"))
      (node (ref "U4") (pin "112") (pinfunction "VCL_F(FLASH)_112") (pintype "bidirectional"))
    )
    (net (code "161") (name "VDD") (class "Default")
      (node (ref "C1") (pin "P$2") (pinfunction "2_P$2") (pintype "passive"))
      (node (ref "C10") (pin "P$2") (pinfunction "2_P$2") (pintype "passive"))
      (node (ref "C13") (pin "P$2") (pinfunction "2_P$2") (pintype "passive"))
      (node (ref "C14") (pin "P$2") (pinfunction "2_P$2") (pintype "passive"))
      (node (ref "C2") (pin "P$2") (pinfunction "2_P$2") (pintype "passive"))
      (node (ref "C30") (pin "P$2") (pinfunction "2_P$2") (pintype "passive"))
      (node (ref "C32") (pin "P$1") (pinfunction "1_P$1") (pintype "passive"))
      (node (ref "C33") (pin "P$1") (pinfunction "1_P$1") (pintype "passive"))
      (node (ref "C34") (pin "P$1") (pinfunction "1_P$1") (pintype "passive"))
      (node (ref "C35") (pin "P$1") (pinfunction "1_P$1") (pintype "passive"))
      (node (ref "C48") (pin "P$1") (pinfunction "1_P$1") (pintype "passive"))
      (node (ref "C49") (pin "P$1") (pinfunction "1_P$1") (pintype "passive"))
      (node (ref "C54") (pin "P$2") (pinfunction "2_P$2") (pintype "passive"))
      (node (ref "C55") (pin "P$2") (pinfunction "2_P$2") (pintype "passive"))
      (node (ref "C56") (pin "P$2") (pinfunction "2_P$2") (pintype "passive"))
      (node (ref "C58") (pin "P$1") (pinfunction "1_P$1") (pintype "passive"))
      (node (ref "C59") (pin "P$1") (pinfunction "1_P$1") (pintype "passive"))
      (node (ref "C60") (pin "P$1") (pinfunction "1_P$1") (pintype "passive"))
      (node (ref "C61") (pin "P$2") (pinfunction "2_P$2") (pintype "passive"))
      (node (ref "FB2/2") (pin "1") (pinfunction "P$1_1") (pintype "bidirectional"))
      (node (ref "J11") (pin "2") (pinfunction "2_2") (pintype "passive"))
      (node (ref "J11") (pin "4") (pinfunction "4_4") (pintype "passive"))
      (node (ref "J9") (pin "4") (pinfunction "SUPPLY_VOLTAGE_4") (pintype "power_in"))
      (node (ref "L3") (pin "2") (pinfunction "P$2_2") (pintype "bidirectional"))
      (node (ref "R13") (pin "P$2") (pinfunction "2_P$2") (pintype "passive"))
      (node (ref "R18") (pin "P$2") (pinfunction "2_P$2") (pintype "passive"))
      (node (ref "R20") (pin "P$1") (pinfunction "1_P$1") (pintype "passive"))
      (node (ref "R21") (pin "P$1") (pinfunction "1_P$1") (pintype "passive"))
      (node (ref "R23") (pin "P$2") (pinfunction "2_P$2") (pintype "passive"))
      (node (ref "R24") (pin "P$2") (pinfunction "2_P$2") (pintype "passive"))
      (node (ref "R26") (pin "P$2") (pinfunction "2_P$2") (pintype "passive"))
      (node (ref "R27") (pin "P$2") (pinfunction "2_P$2") (pintype "passive"))
      (node (ref "R28") (pin "P$2") (pinfunction "2_P$2") (pintype "passive"))
      (node (ref "R29") (pin "P$2") (pinfunction "2_P$2") (pintype "passive"))
      (node (ref "U3") (pin "14") (pinfunction "VDDIO_14") (pintype "power_in"))
      (node (ref "U4") (pin "110") (pinfunction "VCC(IO)5_110") (pintype "bidirectional"))
      (node (ref "U4") (pin "123") (pinfunction "VCC(IO)6_123") (pintype "bidirectional"))
      (node (ref "U4") (pin "138") (pinfunction "VCC(IO)7_138") (pintype "bidirectional"))
      (node (ref "U4") (pin "149") (pinfunction "VCC(IO)8_149") (pintype "bidirectional"))
      (node (ref "U4") (pin "154") (pinfunction "VREFH_154") (pintype "bidirectional"))
      (node (ref "U4") (pin "155") (pinfunction "AVCC0_155") (pintype "bidirectional"))
      (node (ref "U4") (pin "158") (pinfunction "VREFH0_158") (pintype "bidirectional"))
      (node (ref "U4") (pin "171") (pinfunction "VCC(IO)9_171") (pintype "bidirectional"))
      (node (ref "U4") (pin "25") (pinfunction "VCC1_25") (pintype "bidirectional"))
      (node (ref "U4") (pin "26") (pinfunction "AVCC_SUBHS_26") (pintype "bidirectional"))
      (node (ref "U4") (pin "34") (pinfunction "VCC_USBHS_34") (pintype "bidirectional"))
      (node (ref "U4") (pin "48") (pinfunction "VCC_USB_48") (pintype "bidirectional"))
      (node (ref "U4") (pin "61") (pinfunction "VCC(IO)2_61") (pintype "bidirectional"))
      (node (ref "U4") (pin "84") (pinfunction "VCC(IO)3_84") (pintype "bidirectional"))
      (node (ref "U4") (pin "97") (pinfunction "VCC(IO)4_97") (pintype "bidirectional"))
    )
    (net (code "162") (name "VDD5") (class "Default")
      (node (ref "C5") (pin "P$1") (pinfunction "1_P$1") (pintype "passive"))
      (node (ref "C8") (pin "P$1") (pinfunction "1_P$1") (pintype "passive"))
      (node (ref "J1") (pin "P$3") (pinfunction "P$3_P$3") (pintype "bidirectional"))
      (node (ref "R1") (pin "P$2") (pinfunction "2_P$2") (pintype "passive"))
      (node (ref "R12") (pin "P$2") (pinfunction "2_P$2") (pintype "passive"))
      (node (ref "U2") (pin "4") (pinfunction "VIN_4") (pintype "input"))
    )
    (net (code "163") (name "VDDIN") (class "Default")
      (node (ref "J1") (pin "P$2") (pinfunction "P$2_P$2") (pintype "bidirectional"))
      (node (ref "L3") (pin "1") (pinfunction "P$1_1") (pintype "bidirectional"))
    )
    (net (code "164") (name "VDD_1.2") (class "Default")
      (node (ref "C45") (pin "P$1") (pinfunction "1_P$1") (pintype "passive"))
      (node (ref "C46") (pin "P$1") (pinfunction "1_P$1") (pintype "passive"))
      (node (ref "U3") (pin "1") (pinfunction "VDD_1.2_1") (pintype "power_in"))
    )
    (net (code "165") (name "XCIN") (class "Default")
      (node (ref "C50") (pin "P$1") (pinfunction "1_P$1") (pintype "passive"))
      (node (ref "U4") (pin "20") (pinfunction "XCIN_20") (pintype "bidirectional"))
      (node (ref "X3") (pin "P$1") (pinfunction "P$1_P$1") (pintype "bidirectional"))
    )
    (net (code "166") (name "XCOUT") (class "Default")
      (node (ref "C51") (pin "P$1") (pinfunction "1_P$1") (pintype "passive"))
      (node (ref "U4") (pin "21") (pinfunction "XCOUT_21") (pintype "bidirectional"))
      (node (ref "X3") (pin "P$2") (pinfunction "P$2_P$2") (pintype "bidirectional"))
    )
    (net (code "167") (name "XII") (class "Default")
      (node (ref "C42") (pin "P$1") (pinfunction "1_P$1") (pintype "passive"))
      (node (ref "U3") (pin "8") (pinfunction "XI_8") (pintype "input"))
      (node (ref "U5") (pin "1") (pinfunction "1_1") (pintype "bidirectional"))
    )
    (net (code "168") (name "XOO") (class "Default")
      (node (ref "C41") (pin "P$1") (pinfunction "1_P$1") (pintype "passive"))
      (node (ref "U3") (pin "7") (pinfunction "XO_7") (pintype "output"))
      (node (ref "U5") (pin "3") (pinfunction "3_3") (pintype "bidirectional"))
    )
    (net (code "169") (name "XTAL1") (class "Default")
      (node (ref "C52") (pin "P$1") (pinfunction "1_P$1") (pintype "passive"))
      (node (ref "U4") (pin "23") (pinfunction "P2_13/XTAL_23") (pintype "bidirectional"))
      (node (ref "X4") (pin "1") (pinfunction "1_1") (pintype "bidirectional"))
    )
    (net (code "170") (name "XTAL2") (class "Default")
      (node (ref "C53") (pin "P$1") (pinfunction "1_P$1") (pintype "passive"))
      (node (ref "U4") (pin "24") (pinfunction "P2_12/EXTAL_24") (pintype "bidirectional"))
      (node (ref "X4") (pin "3") (pinfunction "3_3") (pintype "bidirectional"))
    )
    (net (code "171") (name "unconnected-(U4-VBAT-Pad18)") (class "Default")
      (node (ref "U4") (pin "18") (pinfunction "VBAT_18") (pintype "bidirectional"))
    )
  )
)
